# EEZ_DIB_DCP405_r2B6.net
KiCad netlist of a schematic drawn in EAGLE
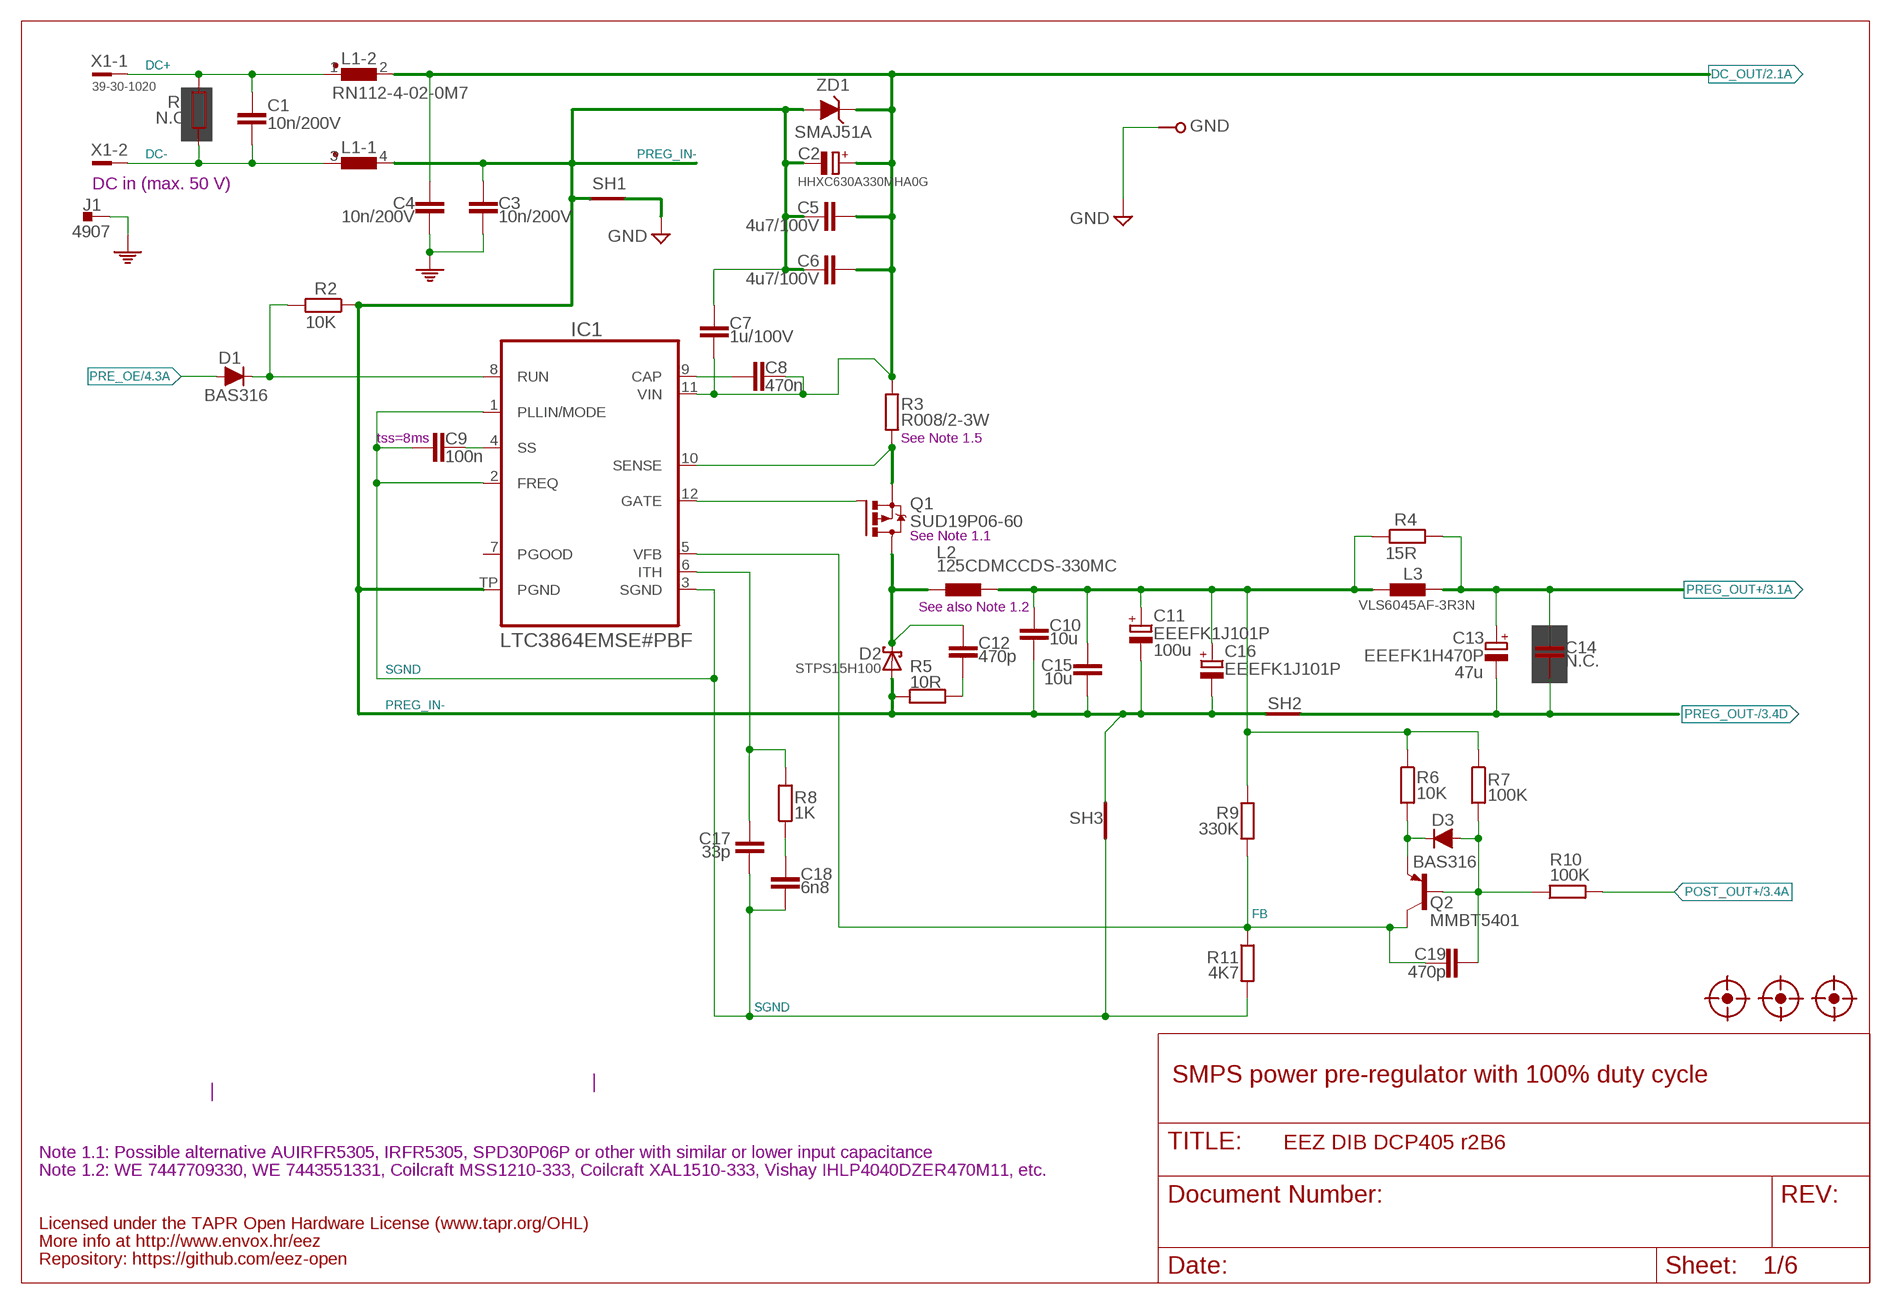
[diagram p0: schematic, sheet 1]
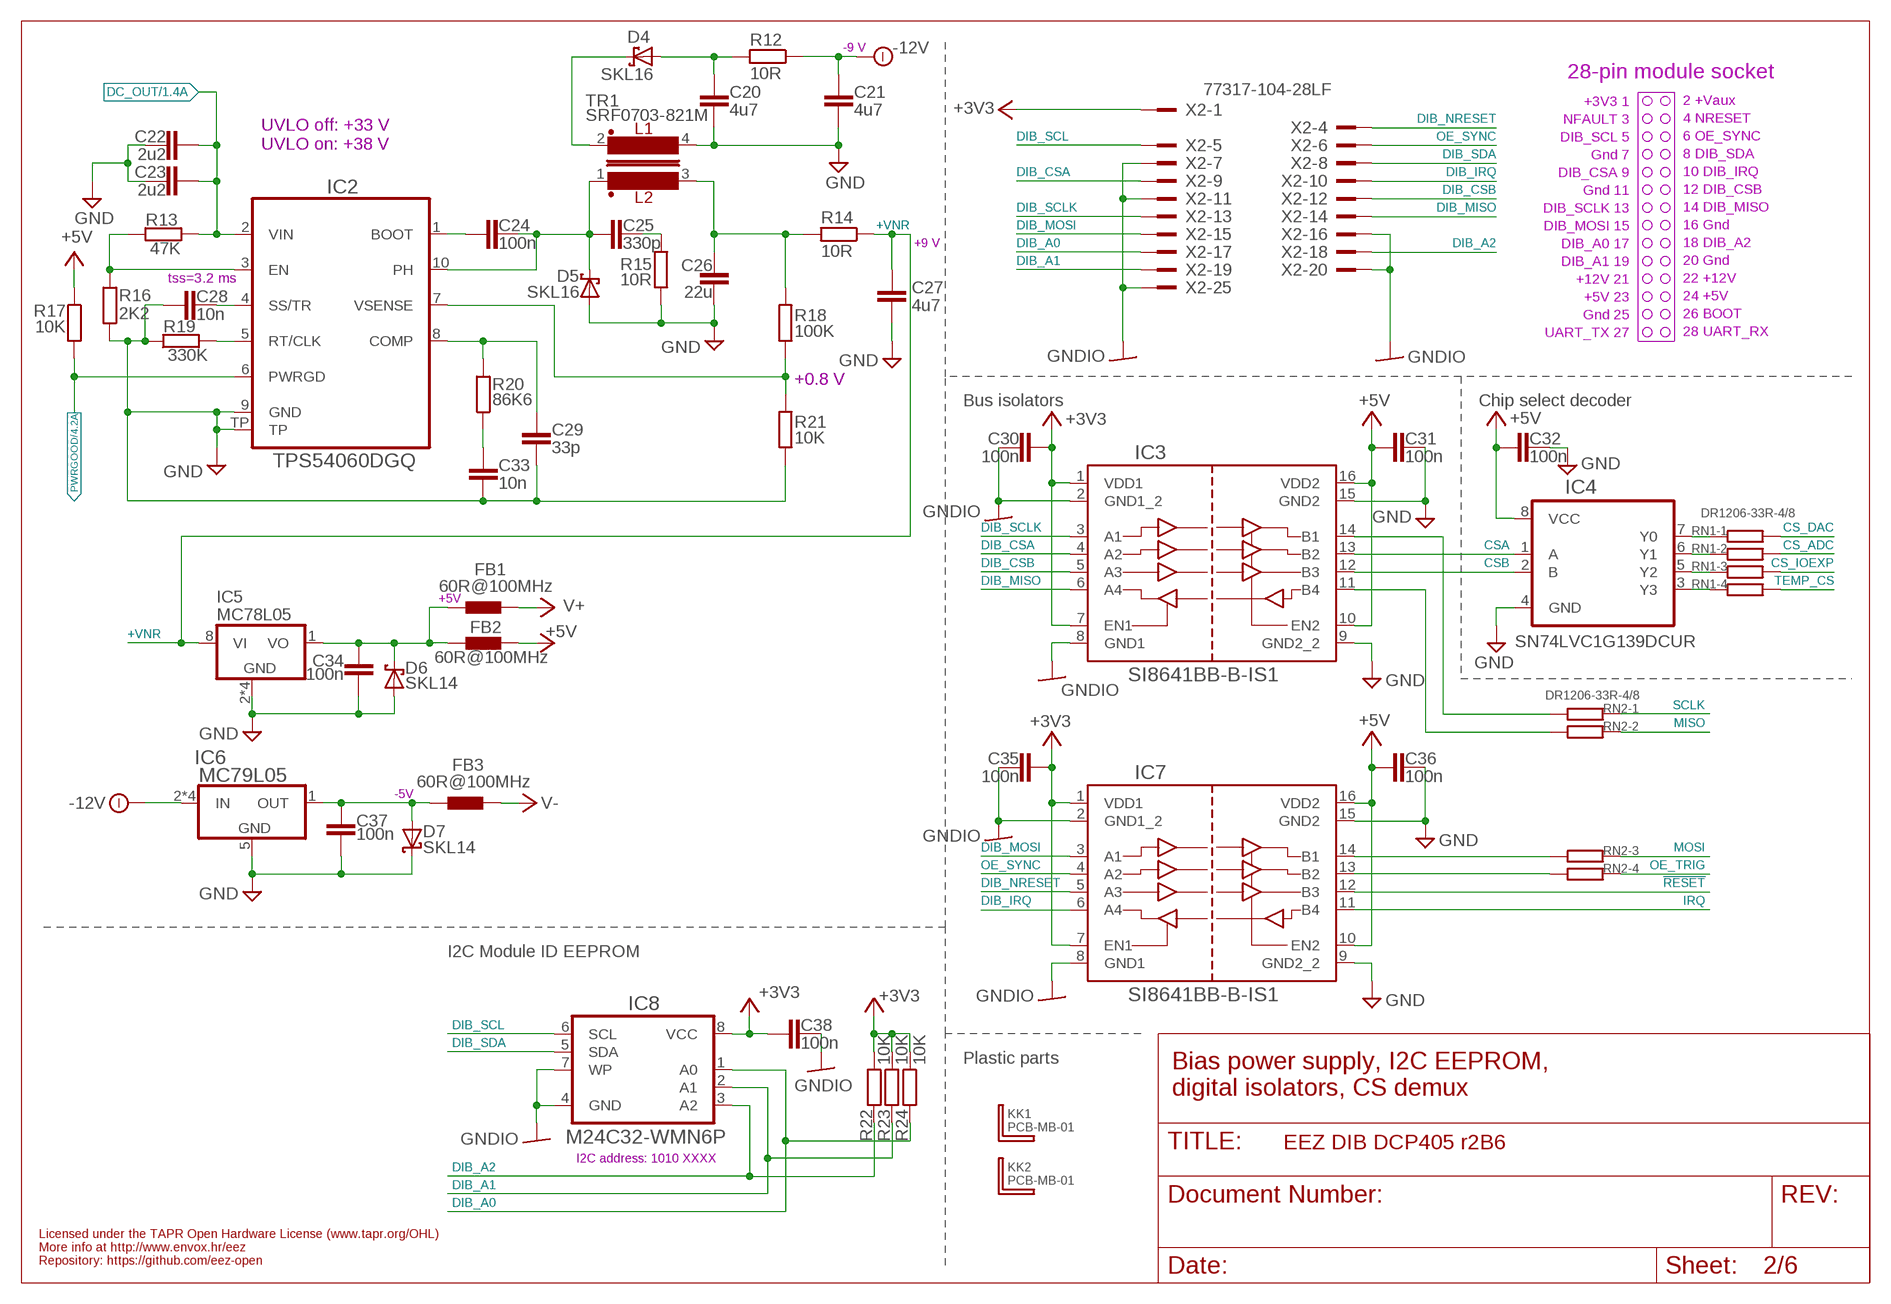
[diagram p1: schematic, sheet 2]
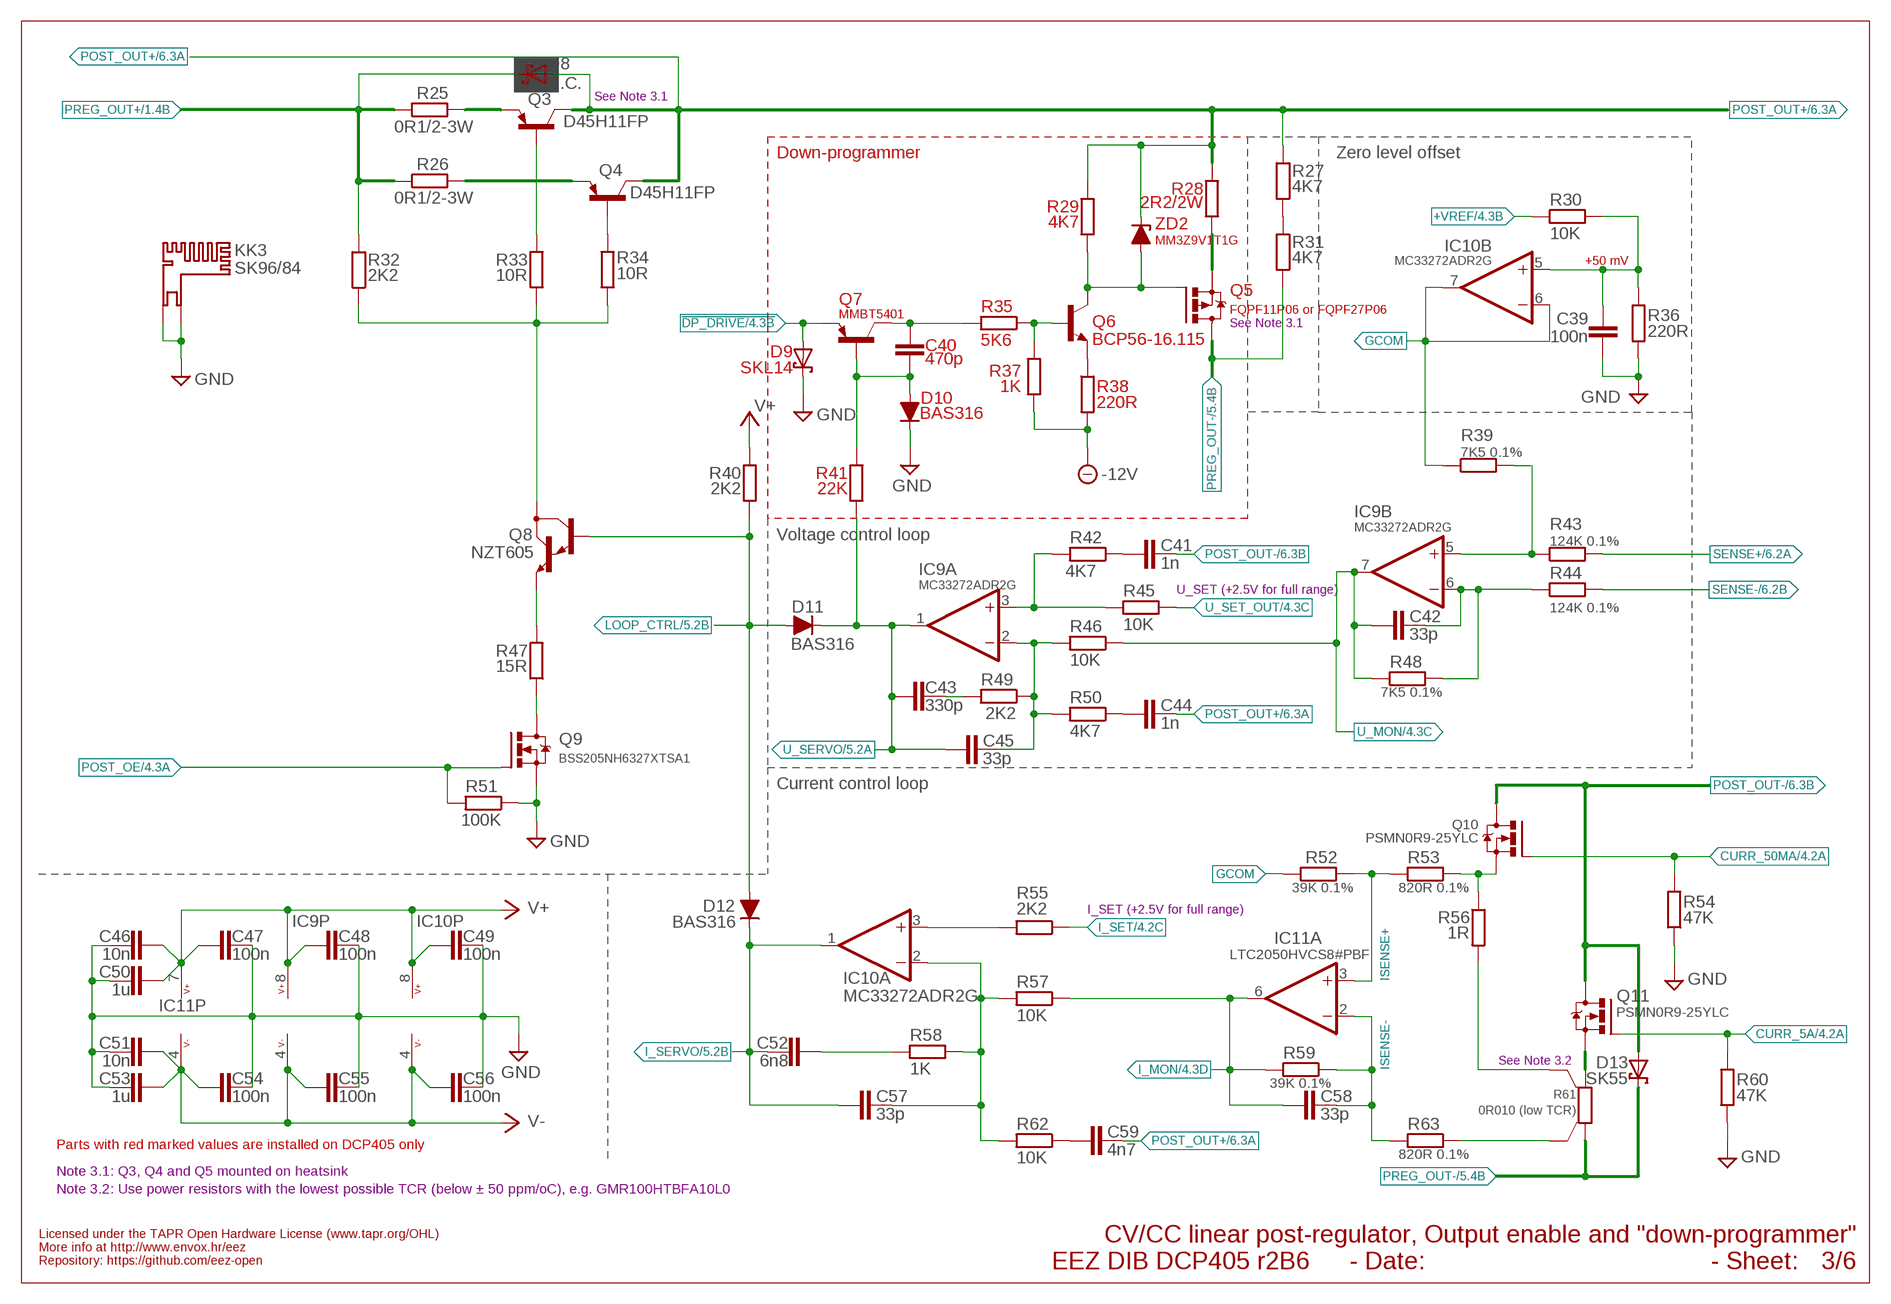
[diagram p2: schematic, sheet 3]
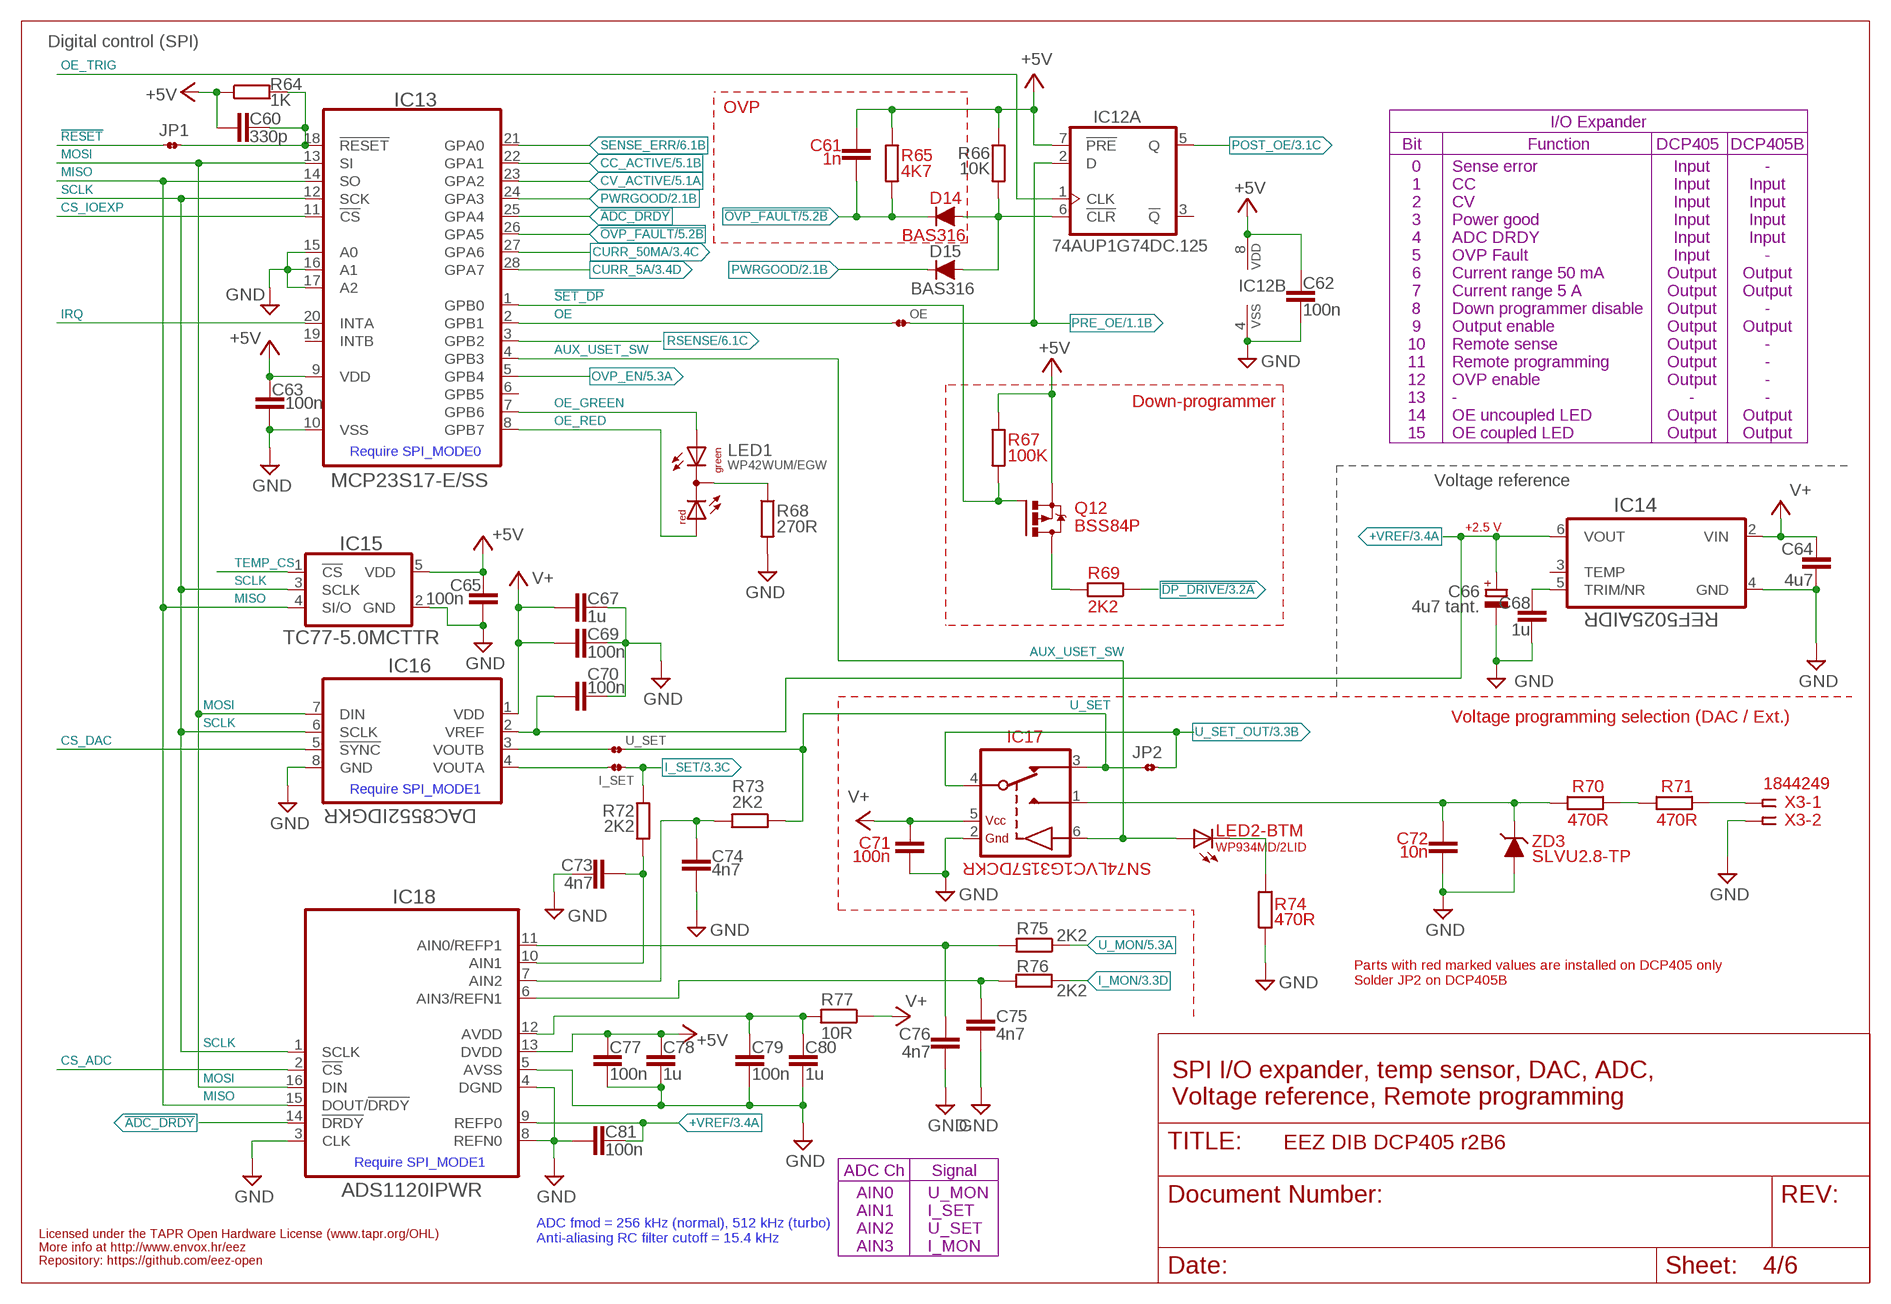
[diagram p3: schematic, sheet 4]
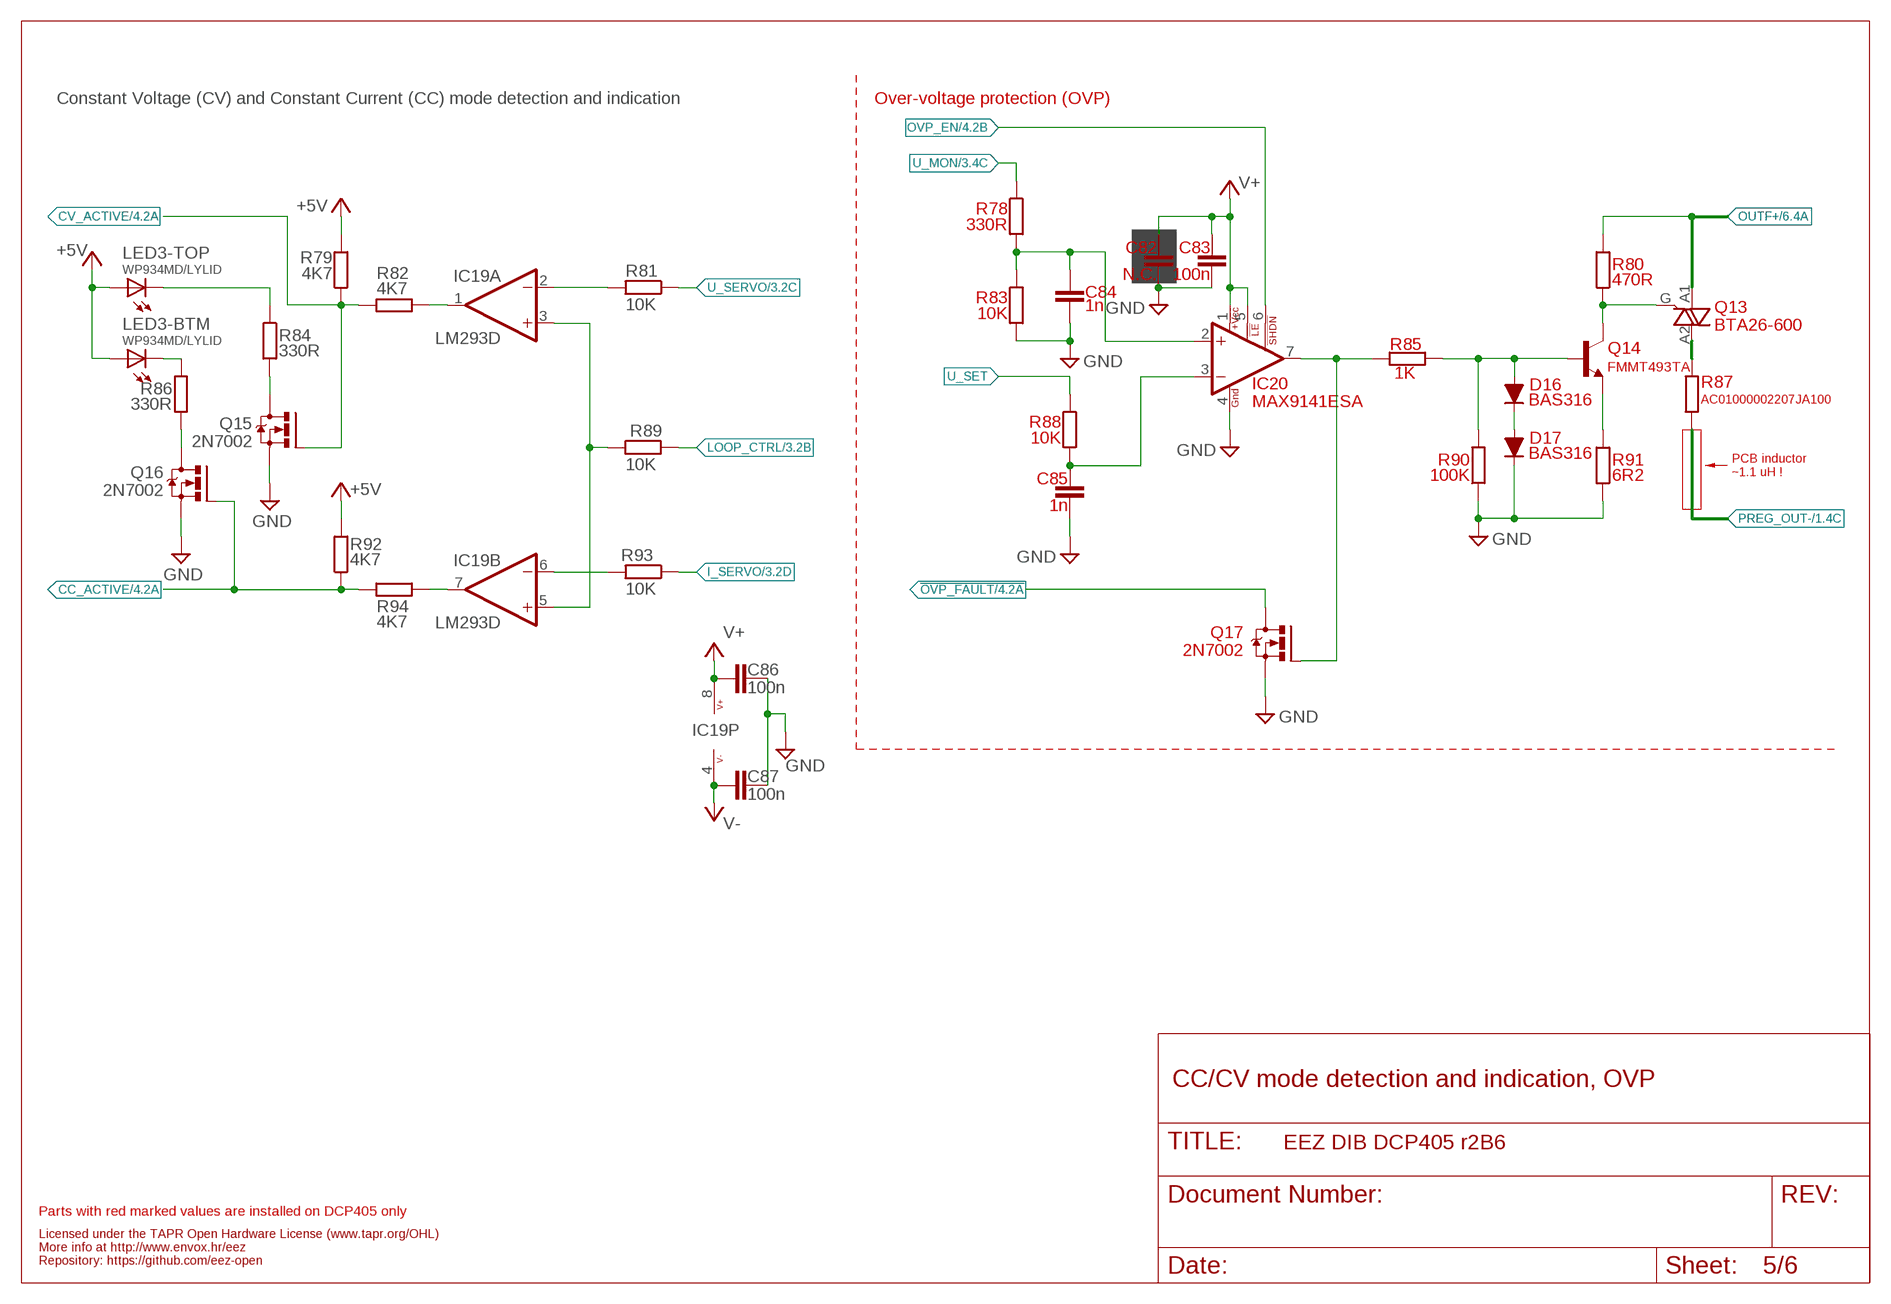
[diagram p4: schematic, sheet 5]
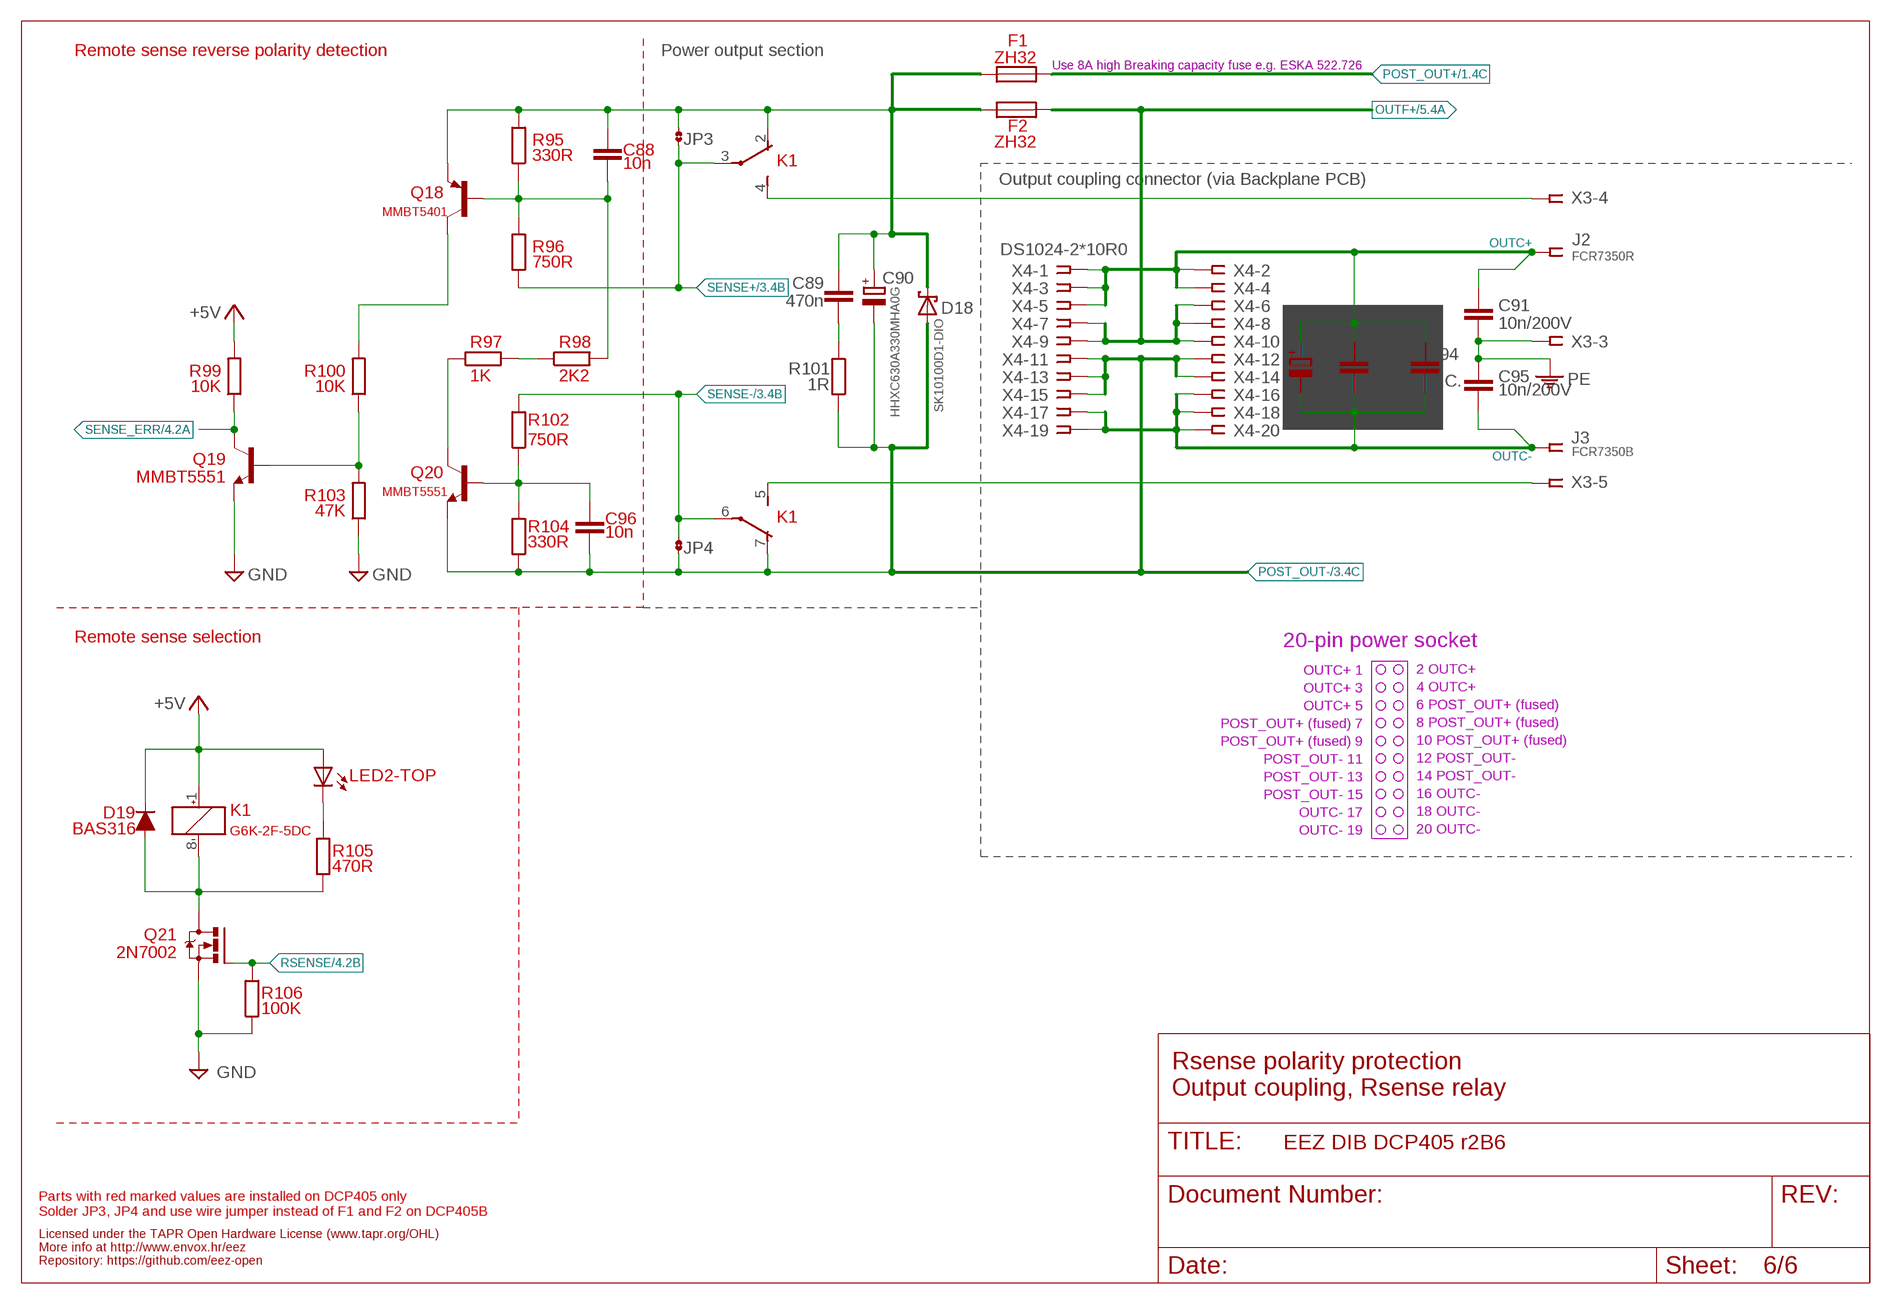
[diagram p5: schematic, sheet 6]

(export (version "E")
  (design (tool "Eeschema 10.0.6"))
  (components
    (comp (ref "C20")
      (value "4u7")
      (footprint "eagle-import:C1206")
      (libsource (lib "eagle-import") (part "C-EUC1206"))
    )
    (comp (ref "C21")
      (value "4u7")
      (footprint "eagle-import:C1206")
      (libsource (lib "eagle-import") (part "C-EUC1206"))
    )
    (comp (ref "C22")
      (value "2u2")
      (footprint "eagle-import:C1206")
      (libsource (lib "eagle-import") (part "C-EUC1206"))
    )
    (comp (ref "C23")
      (value "2u2")
      (footprint "eagle-import:C1206")
      (libsource (lib "eagle-import") (part "C-EUC1206"))
    )
    (comp (ref "C24")
      (value "100n")
      (footprint "eagle-import:C0603")
      (libsource (lib "eagle-import") (part "C-EUC0603"))
    )
    (comp (ref "C25")
      (value "330p")
      (footprint "eagle-import:C0805")
      (libsource (lib "eagle-import") (part "C-EUC0805"))
    )
    (comp (ref "C26")
      (value "22u")
      (footprint "eagle-import:C1210")
      (libsource (lib "eagle-import") (part "C-EUC1210"))
    )
    (comp (ref "C27")
      (value "4u7")
      (footprint "eagle-import:C1206")
      (libsource (lib "eagle-import") (part "C-EUC1206"))
    )
    (comp (ref "C28")
      (value "10n")
      (footprint "eagle-import:C0805")
      (libsource (lib "eagle-import") (part "C-EUC0805"))
    )
    (comp (ref "C29")
      (value "33p")
      (footprint "eagle-import:C0603")
      (libsource (lib "eagle-import") (part "C-EUC0603"))
    )
    (comp (ref "C30")
      (value "100n")
      (footprint "eagle-import:C0603")
      (libsource (lib "eagle-import") (part "C-EUC0603"))
    )
    (comp (ref "C31")
      (value "100n")
      (footprint "eagle-import:C0603")
      (libsource (lib "eagle-import") (part "C-EUC0603"))
    )
    (comp (ref "C32")
      (value "100n")
      (footprint "eagle-import:C0603")
      (libsource (lib "eagle-import") (part "C-EUC0603"))
    )
    (comp (ref "C33")
      (value "10n")
      (footprint "eagle-import:C0805")
      (libsource (lib "eagle-import") (part "C-EUC0805"))
    )
    (comp (ref "C34")
      (value "100n")
      (footprint "eagle-import:C0603")
      (libsource (lib "eagle-import") (part "C-EUC0603"))
    )
    (comp (ref "C35")
      (value "100n")
      (footprint "eagle-import:C0603")
      (libsource (lib "eagle-import") (part "C-EUC0603"))
    )
    (comp (ref "C36")
      (value "100n")
      (footprint "eagle-import:C0603")
      (libsource (lib "eagle-import") (part "C-EUC0603"))
    )
    (comp (ref "C37")
      (value "100n")
      (footprint "eagle-import:C0603")
      (libsource (lib "eagle-import") (part "C-EUC0603"))
    )
    (comp (ref "C38")
      (value "100n")
      (footprint "eagle-import:C0603")
      (libsource (lib "eagle-import") (part "C-EUC0603"))
    )
    (comp (ref "D4")
      (value "SKL16")
      (footprint "eagle-import:SOD123")
      (libsource (lib "eagle-import") (part "SCHOTTKYSOD123"))
    )
    (comp (ref "D5")
      (value "SKL16")
      (footprint "eagle-import:SOD123")
      (libsource (lib "eagle-import") (part "SCHOTTKYSOD123"))
    )
    (comp (ref "D6")
      (value "SKL14")
      (footprint "eagle-import:SOD123")
      (libsource (lib "eagle-import") (part "SCHOTTKYSOD123"))
    )
    (comp (ref "D7")
      (value "SKL14")
      (footprint "eagle-import:SOD123")
      (libsource (lib "eagle-import") (part "SCHOTTKYSOD123"))
    )
    (comp (ref "FB1")
      (value "60R@100MHz")
      (footprint "eagle-import:BEAD0603")
      (libsource (lib "eagle-import") (part "FERRITE_BEAD0603"))
    )
    (comp (ref "FB2")
      (value "60R@100MHz")
      (footprint "eagle-import:BEAD0603")
      (libsource (lib "eagle-import") (part "FERRITE_BEAD0603"))
    )
    (comp (ref "FB3")
      (value "60R@100MHz")
      (footprint "eagle-import:BEAD0603")
      (libsource (lib "eagle-import") (part "FERRITE_BEAD0603"))
    )
    (comp (ref "IC2")
      (value "TPS54060DGQ")
      (footprint "eagle-import:SOP50P490X110-11N")
      (fields (field (name "MPN") "TPS54060ADGQ"))
      (libsource (lib "eagle-import") (part "TPS54060DGQ"))
    )
    (comp (ref "IC3")
      (value "SI8641BB-B-IS1")
      (footprint "eagle-import:SOIC-16")
      (libsource (lib "eagle-import") (part "SI8641NSOIC-16"))
    )
    (comp (ref "IC4")
      (value "SN74LVC1G139DCUR")
      (footprint "eagle-import:DCU8")
      (libsource (lib "eagle-import") (part "SN74LVC1G139-VSSOP"))
    )
    (comp (ref "IC5")
      (value "MC78L05")
      (footprint "eagle-import:SOIC127P600X173-8N")
      (libsource (lib "eagle-import") (part "MC78LXXSOIC8"))
    )
    (comp (ref "IC6")
      (value "MC79L05")
      (footprint "eagle-import:SOIC127P600X173-8N")
      (libsource (lib "eagle-import") (part "MC79LXXSOIC"))
    )
    (comp (ref "IC7")
      (value "SI8641BB-B-IS1")
      (footprint "eagle-import:SOIC-16")
      (libsource (lib "eagle-import") (part "SI8641NSOIC-16"))
    )
    (comp (ref "IC8")
      (value "M24C32-WMN6P")
      (footprint "eagle-import:SOIC127P600X173-8N")
      (libsource (lib "eagle-import") (part "AT24CXXSOIC8"))
    )
    (comp (ref "KK1")
      (value "PCB-MB-01")
      (footprint "eagle-import:PCB-MB")
      (libsource (lib "eagle-import") (part "PCB-MB"))
    )
    (comp (ref "KK2")
      (value "PCB-MB-01")
      (footprint "eagle-import:PCB-MB")
      (libsource (lib "eagle-import") (part "PCB-MB"))
    )
    (comp (ref "R12")
      (value "10R")
      (footprint "eagle-import:R1206")
      (libsource (lib "eagle-import") (part "R-EU_R1206"))
    )
    (comp (ref "R13")
      (value "47K")
      (footprint "eagle-import:R0805")
      (libsource (lib "eagle-import") (part "R-EU_R0805"))
    )
    (comp (ref "R14")
      (value "10R")
      (footprint "eagle-import:R1206")
      (libsource (lib "eagle-import") (part "R-EU_R1206"))
    )
    (comp (ref "R15")
      (value "10R")
      (footprint "eagle-import:R1206")
      (libsource (lib "eagle-import") (part "R-EU_R1206"))
    )
    (comp (ref "R16")
      (value "2K2")
      (footprint "eagle-import:R0805")
      (libsource (lib "eagle-import") (part "R-EU_R0805"))
    )
    (comp (ref "R17")
      (value "10K")
      (footprint "eagle-import:R0805")
      (libsource (lib "eagle-import") (part "R-EU_R0805"))
    )
    (comp (ref "R18")
      (value "100K")
      (footprint "eagle-import:R0805")
      (libsource (lib "eagle-import") (part "R-EU_R0805"))
    )
    (comp (ref "R19")
      (value "330K")
      (footprint "eagle-import:R0805")
      (libsource (lib "eagle-import") (part "R-EU_R0805"))
    )
    (comp (ref "R20")
      (value "86K6")
      (footprint "eagle-import:R0805")
      (libsource (lib "eagle-import") (part "R-EU_R0805"))
    )
    (comp (ref "R21")
      (value "10K")
      (footprint "eagle-import:R0805")
      (libsource (lib "eagle-import") (part "R-EU_R0805"))
    )
    (comp (ref "R22")
      (value "10K")
      (footprint "eagle-import:R0805")
      (libsource (lib "eagle-import") (part "R-EU_R0805"))
    )
    (comp (ref "R23")
      (value "10K")
      (footprint "eagle-import:R0805")
      (libsource (lib "eagle-import") (part "R-EU_R0805"))
    )
    (comp (ref "R24")
      (value "10K")
      (footprint "eagle-import:R0805")
      (libsource (lib "eagle-import") (part "R-EU_R0805"))
    )
    (comp (ref "RN1")
      (value "DR1206-33R-4/8")
      (footprint "eagle-import:CAY16")
      (libsource (lib "eagle-import") (part "R_ARRAY4"))
    )
    (comp (ref "RN2")
      (value "DR1206-33R-4/8")
      (footprint "eagle-import:CAY16")
      (libsource (lib "eagle-import") (part "R_ARRAY4"))
    )
    (comp (ref "TR1")
      (value "SRF0703-821M")
      (footprint "eagle-import:SRF0703")
      (libsource (lib "eagle-import") (part "BOURNS_SRF0703INV"))
    )
    (comp (ref "X2")
      (value "77317-104-28LF")
      (footprint "eagle-import:77317-104-28LF")
      (libsource (lib "eagle-import") (part "77317-104-28LF"))
    )
    (comp (ref "C82")
      (value "N.C.")
      (footprint "eagle-import:C0805")
      (libsource (lib "eagle-import") (part "C-EUC0805"))
    )
    (comp (ref "C83")
      (value "100n")
      (footprint "eagle-import:C0603")
      (libsource (lib "eagle-import") (part "C-EUC0603"))
    )
    (comp (ref "C84")
      (value "1n")
      (footprint "eagle-import:C0805")
      (libsource (lib "eagle-import") (part "C-EUC0805"))
    )
    (comp (ref "C85")
      (value "1n")
      (footprint "eagle-import:C0805")
      (libsource (lib "eagle-import") (part "C-EUC0805"))
    )
    (comp (ref "C86")
      (value "100n")
      (footprint "eagle-import:C0603")
      (libsource (lib "eagle-import") (part "C-EUC0603"))
    )
    (comp (ref "C87")
      (value "100n")
      (footprint "eagle-import:C0603")
      (libsource (lib "eagle-import") (part "C-EUC0603"))
    )
    (comp (ref "D16")
      (value "BAS316")
      (footprint "eagle-import:SOD323-R")
      (libsource (lib "eagle-import") (part "DIODESOD323R"))
    )
    (comp (ref "D17")
      (value "BAS316")
      (footprint "eagle-import:SOD323-R")
      (libsource (lib "eagle-import") (part "DIODESOD323R"))
    )
    (comp (ref "IC19")
      (value "LM293D")
      (footprint "eagle-import:SOIC127P600X173-8N")
      (libsource (lib "eagle-import") (part "LM293D"))
    )
    (comp (ref "IC20")
      (value "MAX9141ESA")
      (footprint "eagle-import:SOIC127P600X173-8N")
      (libsource (lib "eagle-import") (part "MAX9141ESA"))
    )
    (comp (ref "LED3")
      (value "WP934MD/LYLID")
      (footprint "eagle-import:WP934MD")
      (libsource (lib "eagle-import") (part "WP934MD/LYLID"))
    )
    (comp (ref "Q13")
      (value "BTA26-600")
      (footprint "eagle-import:TOP3_TRIAC_NOHOLE")
      (libsource (lib "eagle-import") (part "BTA41-2"))
    )
    (comp (ref "Q14")
      (value "FMMT493TA")
      (footprint "eagle-import:SOT23-BEC")
      (libsource (lib "eagle-import") (part "-NPN-SOT23-BECMMBT5551LT1"))
    )
    (comp (ref "Q15")
      (value "2N7002")
      (footprint "eagle-import:SOT103P240X110-3N")
      (fields (field (name "MPN") "2N7002-7-F"))
      (libsource (lib "eagle-import") (part "2N7002"))
    )
    (comp (ref "Q16")
      (value "2N7002")
      (footprint "eagle-import:SOT103P240X110-3N")
      (fields (field (name "MPN") "2N7002-7-F"))
      (libsource (lib "eagle-import") (part "2N7002"))
    )
    (comp (ref "Q17")
      (value "2N7002")
      (footprint "eagle-import:SOT103P240X110-3N")
      (fields
        (field (name "MPN") "2N7002-7-F")
        (field (name "MPN_1") "2N7002-7-F")
        (field (name "OC_FARNELL") "1713823")
        (field (name "OC_NEWARK") "25R5679")
        (field (name "PACKAGE") "SOT-23-3")
        (field (name "SUPPLIER") "DIODES INC.")
      )
      (libsource (lib "eagle-import") (part "2N7002"))
    )
    (comp (ref "R78")
      (value "330R")
      (footprint "eagle-import:R0805")
      (libsource (lib "eagle-import") (part "R-EU_R0805"))
    )
    (comp (ref "R79")
      (value "4K7")
      (footprint "eagle-import:R0805")
      (libsource (lib "eagle-import") (part "R-EU_R0805"))
    )
    (comp (ref "R80")
      (value "470R")
      (footprint "eagle-import:R0805")
      (libsource (lib "eagle-import") (part "R-EU_R0805"))
    )
    (comp (ref "R81")
      (value "10K")
      (footprint "eagle-import:R0805")
      (libsource (lib "eagle-import") (part "R-EU_R0805"))
    )
    (comp (ref "R82")
      (value "4K7")
      (footprint "eagle-import:R0805")
      (libsource (lib "eagle-import") (part "R-EU_R0805"))
    )
    (comp (ref "R83")
      (value "10K")
      (footprint "eagle-import:R0805")
      (libsource (lib "eagle-import") (part "R-EU_R0805"))
    )
    (comp (ref "R84")
      (value "330R")
      (footprint "eagle-import:R0805")
      (libsource (lib "eagle-import") (part "R-EU_R0805"))
    )
    (comp (ref "R85")
      (value "1K")
      (footprint "eagle-import:R0805")
      (libsource (lib "eagle-import") (part "R-EU_R0805"))
    )
    (comp (ref "R86")
      (value "330R")
      (footprint "eagle-import:R0805")
      (libsource (lib "eagle-import") (part "R-EU_R0805"))
    )
    (comp (ref "R87")
      (value "AC01000002207JA100")
      (footprint "eagle-import:0411_15")
      (libsource (lib "eagle-import") (part "R-EU_0411/15"))
    )
    (comp (ref "R88")
      (value "10K")
      (footprint "eagle-import:R0805")
      (libsource (lib "eagle-import") (part "R-EU_R0805"))
    )
    (comp (ref "R89")
      (value "10K")
      (footprint "eagle-import:R0805")
      (libsource (lib "eagle-import") (part "R-EU_R0805"))
    )
    (comp (ref "R90")
      (value "100K")
      (footprint "eagle-import:R0805")
      (libsource (lib "eagle-import") (part "R-EU_R0805"))
    )
    (comp (ref "R91")
      (value "6R2")
      (footprint "eagle-import:R0805")
      (libsource (lib "eagle-import") (part "R-EU_R0805"))
    )
    (comp (ref "R92")
      (value "4K7")
      (footprint "eagle-import:R0805")
      (libsource (lib "eagle-import") (part "R-EU_R0805"))
    )
    (comp (ref "R93")
      (value "10K")
      (footprint "eagle-import:R0805")
      (libsource (lib "eagle-import") (part "R-EU_R0805"))
    )
    (comp (ref "R94")
      (value "4K7")
      (footprint "eagle-import:R0805")
      (libsource (lib "eagle-import") (part "R-EU_R0805"))
    )
    (comp (ref "C39")
      (value "100n")
      (footprint "eagle-import:C0603")
      (libsource (lib "eagle-import") (part "C-EUC0603"))
    )
    (comp (ref "C40")
      (value "470p")
      (footprint "eagle-import:C0805")
      (libsource (lib "eagle-import") (part "C-EUC0805"))
    )
    (comp (ref "C41")
      (value "1n")
      (footprint "eagle-import:C0805")
      (libsource (lib "eagle-import") (part "C-EUC0805"))
    )
    (comp (ref "C42")
      (value "33p")
      (footprint "eagle-import:C0805")
      (libsource (lib "eagle-import") (part "C-EUC0805"))
    )
    (comp (ref "C43")
      (value "330p")
      (footprint "eagle-import:C0805")
      (libsource (lib "eagle-import") (part "C-EUC0805"))
    )
    (comp (ref "C44")
      (value "1n")
      (footprint "eagle-import:C0805")
      (libsource (lib "eagle-import") (part "C-EUC0805"))
    )
    (comp (ref "C45")
      (value "33p")
      (footprint "eagle-import:C0805")
      (libsource (lib "eagle-import") (part "C-EUC0805"))
    )
    (comp (ref "C46")
      (value "10n")
      (footprint "eagle-import:C0805")
      (libsource (lib "eagle-import") (part "C-EUC0805"))
    )
    (comp (ref "C47")
      (value "100n")
      (footprint "eagle-import:C0603")
      (libsource (lib "eagle-import") (part "C-EUC0603"))
    )
    (comp (ref "C48")
      (value "100n")
      (footprint "eagle-import:C0603")
      (libsource (lib "eagle-import") (part "C-EUC0603"))
    )
    (comp (ref "C49")
      (value "100n")
      (footprint "eagle-import:C0603")
      (libsource (lib "eagle-import") (part "C-EUC0603"))
    )
    (comp (ref "C50")
      (value "1u")
      (footprint "eagle-import:C0805")
      (libsource (lib "eagle-import") (part "C-EUC0805"))
    )
    (comp (ref "C51")
      (value "10n")
      (footprint "eagle-import:C0805")
      (libsource (lib "eagle-import") (part "C-EUC0805"))
    )
    (comp (ref "C52")
      (value "6n8")
      (footprint "eagle-import:C0805")
      (libsource (lib "eagle-import") (part "C-EUC0805"))
    )
    (comp (ref "C53")
      (value "1u")
      (footprint "eagle-import:C0805")
      (libsource (lib "eagle-import") (part "C-EUC0805"))
    )
    (comp (ref "C54")
      (value "100n")
      (footprint "eagle-import:C0603")
      (libsource (lib "eagle-import") (part "C-EUC0603"))
    )
    (comp (ref "C55")
      (value "100n")
      (footprint "eagle-import:C0603")
      (libsource (lib "eagle-import") (part "C-EUC0603"))
    )
    (comp (ref "C56")
      (value "100n")
      (footprint "eagle-import:C0603")
      (libsource (lib "eagle-import") (part "C-EUC0603"))
    )
    (comp (ref "C57")
      (value "33p")
      (footprint "eagle-import:C0805")
      (libsource (lib "eagle-import") (part "C-EUC0805"))
    )
    (comp (ref "C58")
      (value "33p")
      (footprint "eagle-import:C0805")
      (libsource (lib "eagle-import") (part "C-EUC0805"))
    )
    (comp (ref "C59")
      (value "4n7")
      (footprint "eagle-import:C0805")
      (libsource (lib "eagle-import") (part "C-EUC0805"))
    )
    (comp (ref "D8")
      (value "N.C.")
      (footprint "eagle-import:SOD123")
      (libsource (lib "eagle-import") (part "SCHOTTKYSOD123"))
    )
    (comp (ref "D9")
      (value "SKL14")
      (footprint "eagle-import:SOD123")
      (libsource (lib "eagle-import") (part "SCHOTTKYSOD123"))
    )
    (comp (ref "D10")
      (value "BAS316")
      (footprint "eagle-import:SOD323-R")
      (libsource (lib "eagle-import") (part "DIODESOD323R"))
    )
    (comp (ref "D11")
      (value "BAS316")
      (footprint "eagle-import:SOD323-R")
      (libsource (lib "eagle-import") (part "DIODESOD323R"))
    )
    (comp (ref "D12")
      (value "BAS316")
      (footprint "eagle-import:SOD323-R")
      (libsource (lib "eagle-import") (part "DIODESOD323R"))
    )
    (comp (ref "D13")
      (value "SK55")
      (footprint "eagle-import:SMB")
      (libsource (lib "eagle-import") (part "SCHOTTKYSMB"))
    )
    (comp (ref "IC9")
      (value "MC33272ADR2G")
      (footprint "eagle-import:SOIC127P600X173-8N")
      (libsource (lib "eagle-import") (part "TL072SOIC8"))
    )
    (comp (ref "IC10")
      (value "MC33272ADR2G")
      (footprint "eagle-import:SOIC127P600X173-8N")
      (libsource (lib "eagle-import") (part "TL072SOIC8"))
    )
    (comp (ref "IC11")
      (value "LTC2050HVCS8#PBF")
      (footprint "eagle-import:SOIC127P600X173-8N")
      (libsource (lib "eagle-import") (part "OP27GSZSO8"))
    )
    (comp (ref "KK3")
      (value "SK96/84")
      (footprint "eagle-import:SK96_84")
      (libsource (lib "eagle-import") (part "SK96/84"))
    )
    (comp (ref "Q3")
      (value "D45H11FP")
      (footprint "eagle-import:TO220FP-V")
      (libsource (lib "eagle-import") (part "D45H11-FPV"))
    )
    (comp (ref "Q4")
      (value "D45H11FP")
      (footprint "eagle-import:TO220FP-V")
      (libsource (lib "eagle-import") (part "D45H11-FPV"))
    )
    (comp (ref "Q5")
      (value "FQPF11P06 or FQPF27P06")
      (footprint "eagle-import:TO220FP-V")
      (libsource (lib "eagle-import") (part "P-MOSFET-FPV"))
    )
    (comp (ref "Q6")
      (value "BCP56-16.115")
      (footprint "eagle-import:SOT230P700X180-4N")
      (libsource (lib "eagle-import") (part "BCP56"))
    )
    (comp (ref "Q7")
      (value "MMBT5401")
      (footprint "eagle-import:SOT23-BEC")
      (libsource (lib "eagle-import") (part "-PNP-SOT23-BECBC857B"))
    )
    (comp (ref "Q8")
      (value "NZT605")
      (footprint "eagle-import:SOT230P700X180-4N")
      (libsource (lib "eagle-import") (part "NZT605"))
    )
    (comp (ref "Q9")
      (value "BSS205NH6327XTSA1")
      (footprint "eagle-import:SOT103P240X110-3N")
      (fields
        (field (name "MPN") "2N7002-7-F")
        (field (name "MPN_1") "2N7002-7-F")
        (field (name "OC_FARNELL") "1713823")
        (field (name "OC_NEWARK") "25R5679")
        (field (name "PACKAGE") "SOT-23-3")
        (field (name "SUPPLIER") "DIODES INC.")
      )
      (libsource (lib "eagle-import") (part "2N7002"))
    )
    (comp (ref "Q10")
      (value "PSMN0R9-25YLC")
      (footprint "eagle-import:SOT669")
      (libsource (lib "eagle-import") (part "N-MOSFETLFPAK"))
    )
    (comp (ref "Q11")
      (value "PSMN0R9-25YLC")
      (footprint "eagle-import:SOT669")
      (libsource (lib "eagle-import") (part "N-MOSFETLFPAK"))
    )
    (comp (ref "R25")
      (value "0R1/2-3W")
      (footprint "eagle-import:R2512")
      (libsource (lib "eagle-import") (part "R-EU_R2512"))
    )
    (comp (ref "R26")
      (value "0R1/2-3W")
      (footprint "eagle-import:R2512")
      (libsource (lib "eagle-import") (part "R-EU_R2512"))
    )
    (comp (ref "R27")
      (value "4K7")
      (footprint "eagle-import:R0805")
      (libsource (lib "eagle-import") (part "R-EU_R0805"))
    )
    (comp (ref "R28")
      (value "2R2/2W")
      (footprint "eagle-import:R2512")
      (libsource (lib "eagle-import") (part "R-EU_R2512"))
    )
    (comp (ref "R29")
      (value "4K7")
      (footprint "eagle-import:R0805")
      (libsource (lib "eagle-import") (part "R-EU_R0805"))
    )
    (comp (ref "R30")
      (value "10K")
      (footprint "eagle-import:R0805")
      (libsource (lib "eagle-import") (part "R-EU_R0805"))
    )
    (comp (ref "R31")
      (value "4K7")
      (footprint "eagle-import:R0805")
      (libsource (lib "eagle-import") (part "R-EU_R0805"))
    )
    (comp (ref "R32")
      (value "2K2")
      (footprint "eagle-import:R0805")
      (libsource (lib "eagle-import") (part "R-EU_R0805"))
    )
    (comp (ref "R33")
      (value "10R")
      (footprint "eagle-import:R1206")
      (libsource (lib "eagle-import") (part "R-EU_R1206"))
    )
    (comp (ref "R34")
      (value "10R")
      (footprint "eagle-import:R1206")
      (libsource (lib "eagle-import") (part "R-EU_R1206"))
    )
    (comp (ref "R35")
      (value "5K6")
      (footprint "eagle-import:R0805")
      (libsource (lib "eagle-import") (part "R-EU_R0805"))
    )
    (comp (ref "R36")
      (value "220R")
      (footprint "eagle-import:R0805")
      (libsource (lib "eagle-import") (part "R-EU_R0805"))
    )
    (comp (ref "R37")
      (value "1K")
      (footprint "eagle-import:R0805")
      (libsource (lib "eagle-import") (part "R-EU_R0805"))
    )
    (comp (ref "R38")
      (value "220R")
      (footprint "eagle-import:R0805")
      (libsource (lib "eagle-import") (part "R-EU_R0805"))
    )
    (comp (ref "R39")
      (value "7K5 0.1%")
      (footprint "eagle-import:R0805")
      (libsource (lib "eagle-import") (part "R-EU_R0805"))
    )
    (comp (ref "R40")
      (value "2K2")
      (footprint "eagle-import:R0805")
      (libsource (lib "eagle-import") (part "R-EU_R0805"))
    )
    (comp (ref "R41")
      (value "22K")
      (footprint "eagle-import:R0805")
      (libsource (lib "eagle-import") (part "R-EU_R0805"))
    )
    (comp (ref "R42")
      (value "4K7")
      (footprint "eagle-import:R0805")
      (libsource (lib "eagle-import") (part "R-EU_R0805"))
    )
    (comp (ref "R43")
      (value "124K 0.1%")
      (footprint "eagle-import:R0805")
      (libsource (lib "eagle-import") (part "R-EU_R0805"))
    )
    (comp (ref "R44")
      (value "124K 0.1%")
      (footprint "eagle-import:R0805")
      (libsource (lib "eagle-import") (part "R-EU_R0805"))
    )
    (comp (ref "R45")
      (value "10K")
      (footprint "eagle-import:R0805")
      (libsource (lib "eagle-import") (part "R-EU_R0805"))
    )
    (comp (ref "R46")
      (value "10K")
      (footprint "eagle-import:R0805")
      (libsource (lib "eagle-import") (part "R-EU_R0805"))
    )
    (comp (ref "R47")
      (value "15R")
      (footprint "eagle-import:R1206")
      (libsource (lib "eagle-import") (part "R-EU_R1206"))
    )
    (comp (ref "R48")
      (value "7K5 0.1%")
      (footprint "eagle-import:R0805")
      (libsource (lib "eagle-import") (part "R-EU_R0805"))
    )
    (comp (ref "R49")
      (value "2K2")
      (footprint "eagle-import:R0805")
      (libsource (lib "eagle-import") (part "R-EU_R0805"))
    )
    (comp (ref "R50")
      (value "4K7")
      (footprint "eagle-import:R0805")
      (libsource (lib "eagle-import") (part "R-EU_R0805"))
    )
    (comp (ref "R51")
      (value "100K")
      (footprint "eagle-import:R0805")
      (libsource (lib "eagle-import") (part "R-EU_R0805"))
    )
    (comp (ref "R52")
      (value "39K 0.1%")
      (footprint "eagle-import:R0805")
      (libsource (lib "eagle-import") (part "R-EU_R0805"))
    )
    (comp (ref "R53")
      (value "820R 0.1%")
      (footprint "eagle-import:R0805")
      (libsource (lib "eagle-import") (part "R-EU_R0805"))
    )
    (comp (ref "R54")
      (value "47K")
      (footprint "eagle-import:R0805")
      (libsource (lib "eagle-import") (part "R-EU_R0805"))
    )
    (comp (ref "R55")
      (value "2K2")
      (footprint "eagle-import:R0805")
      (libsource (lib "eagle-import") (part "R-EU_R0805"))
    )
    (comp (ref "R56")
      (value "1R")
      (footprint "eagle-import:R1206")
      (libsource (lib "eagle-import") (part "R-EU_R1206"))
    )
    (comp (ref "R57")
      (value "10K")
      (footprint "eagle-import:R0805")
      (libsource (lib "eagle-import") (part "R-EU_R0805"))
    )
    (comp (ref "R58")
      (value "1K")
      (footprint "eagle-import:R0805")
      (libsource (lib "eagle-import") (part "R-EU_R0805"))
    )
    (comp (ref "R59")
      (value "39K 0.1%")
      (footprint "eagle-import:R0805")
      (libsource (lib "eagle-import") (part "R-EU_R0805"))
    )
    (comp (ref "R60")
      (value "47K")
      (footprint "eagle-import:R0805")
      (libsource (lib "eagle-import") (part "R-EU_R0805"))
    )
    (comp (ref "R61")
      (value "0R010 (low TCR)")
      (footprint "eagle-import:R_2512-4WIRE")
      (libsource (lib "eagle-import") (part "R-EU_4WIRE2512"))
    )
    (comp (ref "R62")
      (value "10K")
      (footprint "eagle-import:R0805")
      (libsource (lib "eagle-import") (part "R-EU_R0805"))
    )
    (comp (ref "R63")
      (value "820R 0.1%")
      (footprint "eagle-import:R0805")
      (libsource (lib "eagle-import") (part "R-EU_R0805"))
    )
    (comp (ref "ZD2")
      (value "MM3Z9V1T1G")
      (footprint "eagle-import:SOD323-R")
      (libsource (lib "eagle-import") (part "ZENER-DIODESOD323R"))
    )
    (comp (ref "C60")
      (value "330p")
      (footprint "eagle-import:C0805")
      (libsource (lib "eagle-import") (part "C-EUC0805"))
    )
    (comp (ref "C61")
      (value "1n")
      (footprint "eagle-import:C0805")
      (libsource (lib "eagle-import") (part "C-EUC0805"))
    )
    (comp (ref "C62")
      (value "100n")
      (footprint "eagle-import:C0603")
      (libsource (lib "eagle-import") (part "C-EUC0603"))
    )
    (comp (ref "C63")
      (value "100n")
      (footprint "eagle-import:C0603")
      (libsource (lib "eagle-import") (part "C-EUC0603"))
    )
    (comp (ref "C64")
      (value "4u7")
      (footprint "eagle-import:C1206")
      (libsource (lib "eagle-import") (part "C-EUC1206"))
    )
    (comp (ref "C65")
      (value "100n")
      (footprint "eagle-import:C0603")
      (libsource (lib "eagle-import") (part "C-EUC0603"))
    )
    (comp (ref "C66")
      (value "4u7 tant.")
      (footprint "eagle-import:EC1206")
      (libsource (lib "eagle-import") (part "ECAP1206"))
    )
    (comp (ref "C67")
      (value "1u")
      (footprint "eagle-import:C0805")
      (libsource (lib "eagle-import") (part "C-EUC0805"))
    )
    (comp (ref "C68")
      (value "1u")
      (footprint "eagle-import:C0805")
      (libsource (lib "eagle-import") (part "C-EUC0805"))
    )
    (comp (ref "C69")
      (value "100n")
      (footprint "eagle-import:C0603")
      (libsource (lib "eagle-import") (part "C-EUC0603"))
    )
    (comp (ref "C70")
      (value "100n")
      (footprint "eagle-import:C0603")
      (libsource (lib "eagle-import") (part "C-EUC0603"))
    )
    (comp (ref "C71")
      (value "100n")
      (footprint "eagle-import:C0603")
      (libsource (lib "eagle-import") (part "C-EUC0603"))
    )
    (comp (ref "C72")
      (value "10n")
      (footprint "eagle-import:C0805")
      (libsource (lib "eagle-import") (part "C-EUC0805"))
    )
    (comp (ref "C73")
      (value "4n7")
      (footprint "eagle-import:C0805")
      (libsource (lib "eagle-import") (part "C-EUC0805"))
    )
    (comp (ref "C74")
      (value "4n7")
      (footprint "eagle-import:C0805")
      (libsource (lib "eagle-import") (part "C-EUC0805"))
    )
    (comp (ref "C75")
      (value "4n7")
      (footprint "eagle-import:C0805")
      (libsource (lib "eagle-import") (part "C-EUC0805"))
    )
    (comp (ref "C76")
      (value "4n7")
      (footprint "eagle-import:C0805")
      (libsource (lib "eagle-import") (part "C-EUC0805"))
    )
    (comp (ref "C77")
      (value "100n")
      (footprint "eagle-import:C0603")
      (libsource (lib "eagle-import") (part "C-EUC0603"))
    )
    (comp (ref "C78")
      (value "1u")
      (footprint "eagle-import:C0805")
      (libsource (lib "eagle-import") (part "C-EUC0805"))
    )
    (comp (ref "C79")
      (value "100n")
      (footprint "eagle-import:C0603")
      (libsource (lib "eagle-import") (part "C-EUC0603"))
    )
    (comp (ref "C80")
      (value "1u")
      (footprint "eagle-import:C0805")
      (libsource (lib "eagle-import") (part "C-EUC0805"))
    )
    (comp (ref "C81")
      (value "100n")
      (footprint "eagle-import:C0603")
      (libsource (lib "eagle-import") (part "C-EUC0603"))
    )
    (comp (ref "D14")
      (value "BAS316")
      (footprint "eagle-import:SOD323-R")
      (libsource (lib "eagle-import") (part "DIODESOD323R"))
    )
    (comp (ref "D15")
      (value "BAS316")
      (footprint "eagle-import:SOD323-R")
      (libsource (lib "eagle-import") (part "DIODESOD323R"))
    )
    (comp (ref "IC12")
      (value "74AUP1G74DC.125")
      (footprint "eagle-import:DCU8")
      (libsource (lib "eagle-import") (part "SN74LVC1G74DCTR-VSSOP"))
    )
    (comp (ref "IC13")
      (value "MCP23S17-E/SS")
      (footprint "eagle-import:SOP65P780X200-28N")
      (libsource (lib "eagle-import") (part "MCP23S17-E/SSSSOP"))
    )
    (comp (ref "IC14")
      (value "REF5025AIDR")
      (footprint "eagle-import:SOIC127P600X175-8N")
      (libsource (lib "eagle-import") (part "REF50XX"))
    )
    (comp (ref "IC15")
      (value "TC77-5.0MCTTR")
      (footprint "eagle-import:SOT23-5")
      (libsource (lib "eagle-import") (part "TC77"))
    )
    (comp (ref "IC16")
      (value "DAC8552IDGKR")
      (footprint "eagle-import:DGK8-M")
      (libsource (lib "eagle-import") (part "DAC8552_DGK_8M"))
    )
    (comp (ref "IC17")
      (value "SN74LVC1G3157DCKR")
      (footprint "eagle-import:SOT65P210X110-6N")
      (libsource (lib "eagle-import") (part "SN74LVC1G3157-DCK"))
    )
    (comp (ref "IC18")
      (value "ADS1120IPWR")
      (footprint "eagle-import:PW(R-PDSO-G16)")
      (libsource (lib "eagle-import") (part "ADS1120TSSOP-16"))
    )
    (comp (ref "I_SET")
      (value "JP2-NOCUT")
      (footprint "eagle-import:JP2-NOCUT")
      (libsource (lib "eagle-import") (part "JP2-NOCUT"))
    )
    (comp (ref "JP1")
      (value "JP2-NOCUT")
      (footprint "eagle-import:JP2-NOCUT")
      (libsource (lib "eagle-import") (part "JP2-NOCUT"))
    )
    (comp (ref "JP2")
      (value "JP2-CUT")
      (footprint "eagle-import:JP2-CUT")
      (libsource (lib "eagle-import") (part "JP2-CUT"))
    )
    (comp (ref "LED1")
      (value "WP42WUM/EGW")
      (footprint "eagle-import:L-42WUM-1EGWT")
      (libsource (lib "eagle-import") (part "LED_L-42WUM/1EGWT"))
    )
    (comp (ref "LED2")
      (value "WP934MD/2LID")
      (footprint "eagle-import:WP934MD")
      (libsource (lib "eagle-import") (part "WP934MD/2LID"))
    )
    (comp (ref "OE")
      (value "JP2-NOCUT")
      (footprint "eagle-import:JP2-NOCUT")
      (libsource (lib "eagle-import") (part "JP2-NOCUT"))
    )
    (comp (ref "Q12")
      (value "BSS84P")
      (footprint "eagle-import:SOT95P237X112-3N")
      (fields (field (name "MPN") "IRLML2246TRPBF"))
      (libsource (lib "eagle-import") (part "IRLML2246TRPBF"))
    )
    (comp (ref "R64")
      (value "1K")
      (footprint "eagle-import:R0805")
      (libsource (lib "eagle-import") (part "R-EU_R0805"))
    )
    (comp (ref "R65")
      (value "4K7")
      (footprint "eagle-import:R0805")
      (libsource (lib "eagle-import") (part "R-EU_R0805"))
    )
    (comp (ref "R66")
      (value "10K")
      (footprint "eagle-import:R0805")
      (libsource (lib "eagle-import") (part "R-EU_R0805"))
    )
    (comp (ref "R67")
      (value "100K")
      (footprint "eagle-import:R0805")
      (libsource (lib "eagle-import") (part "R-EU_R0805"))
    )
    (comp (ref "R68")
      (value "270R")
      (footprint "eagle-import:R0805")
      (libsource (lib "eagle-import") (part "R-EU_R0805"))
    )
    (comp (ref "R69")
      (value "2K2")
      (footprint "eagle-import:R0805")
      (libsource (lib "eagle-import") (part "R-EU_R0805"))
    )
    (comp (ref "R70")
      (value "470R")
      (footprint "eagle-import:R0805")
      (libsource (lib "eagle-import") (part "R-EU_R0805"))
    )
    (comp (ref "R71")
      (value "470R")
      (footprint "eagle-import:R0805")
      (libsource (lib "eagle-import") (part "R-EU_R0805"))
    )
    (comp (ref "R72")
      (value "2K2")
      (footprint "eagle-import:R0805")
      (libsource (lib "eagle-import") (part "R-EU_R0805"))
    )
    (comp (ref "R73")
      (value "2K2")
      (footprint "eagle-import:R0805")
      (libsource (lib "eagle-import") (part "R-EU_R0805"))
    )
    (comp (ref "R74")
      (value "470R")
      (footprint "eagle-import:R0805")
      (libsource (lib "eagle-import") (part "R-EU_R0805"))
    )
    (comp (ref "R75")
      (value "2K2")
      (footprint "eagle-import:R0805")
      (libsource (lib "eagle-import") (part "R-EU_R0805"))
    )
    (comp (ref "R76")
      (value "2K2")
      (footprint "eagle-import:R0805")
      (libsource (lib "eagle-import") (part "R-EU_R0805"))
    )
    (comp (ref "R77")
      (value "10R")
      (footprint "eagle-import:R1206")
      (libsource (lib "eagle-import") (part "R-EU_R1206"))
    )
    (comp (ref "U_SET")
      (value "JP2-NOCUT")
      (footprint "eagle-import:JP2-NOCUT")
      (libsource (lib "eagle-import") (part "JP2-NOCUT"))
    )
    (comp (ref "X3")
      (value "1844249")
      (footprint "eagle-import:MC1,5_5-G-3,5")
      (libsource (lib "eagle-import") (part "MC1,5/5-G-3,5"))
    )
    (comp (ref "ZD3")
      (value "SLVU2.8-TP")
      (footprint "eagle-import:SOT23")
      (libsource (lib "eagle-import") (part "SLVU2.8"))
    )
    (comp (ref "C1")
      (value "10n/200V")
      (footprint "eagle-import:C1206")
      (libsource (lib "eagle-import") (part "C-EUC1206"))
    )
    (comp (ref "C2")
      (value "HHXC630A330MHA0G")
      (footprint "eagle-import:CAPAE830X1050N")
      (libsource (lib "eagle-import") (part "ECAPSMD8.3MM/HA0"))
    )
    (comp (ref "C3")
      (value "10n/200V")
      (footprint "eagle-import:C1206")
      (libsource (lib "eagle-import") (part "C-EUC1206"))
    )
    (comp (ref "C4")
      (value "10n/200V")
      (footprint "eagle-import:C1206")
      (libsource (lib "eagle-import") (part "C-EUC1206"))
    )
    (comp (ref "C5")
      (value "4u7/100V")
      (footprint "eagle-import:C1210")
      (libsource (lib "eagle-import") (part "C-EUC1210"))
    )
    (comp (ref "C6")
      (value "4u7/100V")
      (footprint "eagle-import:C1210")
      (libsource (lib "eagle-import") (part "C-EUC1210"))
    )
    (comp (ref "C7")
      (value "1u/100V")
      (footprint "eagle-import:C1206")
      (libsource (lib "eagle-import") (part "C-EUC1206"))
    )
    (comp (ref "C8")
      (value "470n")
      (footprint "eagle-import:C0805")
      (libsource (lib "eagle-import") (part "C-EUC0805"))
    )
    (comp (ref "C9")
      (value "100n")
      (footprint "eagle-import:C0603")
      (libsource (lib "eagle-import") (part "C-EUC0603"))
    )
    (comp (ref "C10")
      (value "10u")
      (footprint "eagle-import:C1210")
      (libsource (lib "eagle-import") (part "C-EUC1210"))
    )
    (comp (ref "C11")
      (value "EEEFK1J101P")
      (footprint "eagle-import:CAPAE1030X1050N")
      (libsource (lib "eagle-import") (part "ECAP10X10"))
    )
    (comp (ref "C12")
      (value "470p")
      (footprint "eagle-import:C0805")
      (libsource (lib "eagle-import") (part "C-EUC0805"))
    )
    (comp (ref "C13")
      (value "EEEFK1H470P")
      (footprint "eagle-import:CAPAE830X1050N")
      (libsource (lib "eagle-import") (part "ECAPSMD8.3MM/HA0"))
    )
    (comp (ref "C14")
      (value "N.C.")
      (footprint "eagle-import:C0805")
      (libsource (lib "eagle-import") (part "C-EUC0805"))
    )
    (comp (ref "C15")
      (value "10u")
      (footprint "eagle-import:C1210")
      (libsource (lib "eagle-import") (part "C-EUC1210"))
    )
    (comp (ref "C16")
      (value "EEEFK1J101P")
      (footprint "eagle-import:CAPAE1030X1050N")
      (libsource (lib "eagle-import") (part "ECAP10X10"))
    )
    (comp (ref "C17")
      (value "33p")
      (footprint "eagle-import:C0805")
      (libsource (lib "eagle-import") (part "C-EUC0805"))
    )
    (comp (ref "C18")
      (value "6n8")
      (footprint "eagle-import:C0805")
      (libsource (lib "eagle-import") (part "C-EUC0805"))
    )
    (comp (ref "C19")
      (value "470p")
      (footprint "eagle-import:C0805")
      (libsource (lib "eagle-import") (part "C-EUC0805"))
    )
    (comp (ref "D1")
      (value "BAS316")
      (footprint "eagle-import:SOD323-R")
      (libsource (lib "eagle-import") (part "DIODESOD323R"))
    )
    (comp (ref "D2")
      (value "STPS15H100")
      (footprint "eagle-import:TO252-L")
      (libsource (lib "eagle-import") (part "SCHOTTKY-DUAL_A_L"))
    )
    (comp (ref "D3")
      (value "BAS316")
      (footprint "eagle-import:SOD323-R")
      (libsource (lib "eagle-import") (part "DIODESOD323R"))
    )
    (comp (ref "FM1")
      (value "FIDUCIAL_2")
      (footprint "eagle-import:FIDUCIAL_DUAL")
      (libsource (lib "eagle-import") (part "FIDUCIAL_2"))
    )
    (comp (ref "FM2")
      (value "FIDUCIAL_2")
      (footprint "eagle-import:FIDUCIAL_DUAL")
      (libsource (lib "eagle-import") (part "FIDUCIAL_2"))
    )
    (comp (ref "FM3")
      (value "FIDUCIAL_2")
      (footprint "eagle-import:FIDUCIAL_DUAL")
      (libsource (lib "eagle-import") (part "FIDUCIAL_2"))
    )
    (comp (ref "GND")
      (value "PCB_TEST_TABSHIELD")
      (footprint "eagle-import:PCB_SHIELD_TAB")
      (libsource (lib "eagle-import") (part "PCB_TEST_TABSHIELD"))
    )
    (comp (ref "IC1")
      (value "LTC3864EMSE#PBF")
      (footprint "eagle-import:LTC_05-08-1666")
      (libsource (lib "eagle-import") (part "LTC3864"))
    )
    (comp (ref "J1")
      (value "4907")
      (footprint "eagle-import:PCB_TAB-4907")
      (libsource (lib "eagle-import") (part "PCB_TAB-4907"))
    )
    (comp (ref "L1")
      (value "RN112-4-02-0M7")
      (footprint "eagle-import:RN112")
      (libsource (lib "eagle-import") (part "RN112"))
    )
    (comp (ref "L2")
      (value "125CDMCCDS-330MC")
      (footprint "eagle-import:125CDMCC_DS")
      (libsource (lib "eagle-import") (part "125CDMCC/DS"))
    )
    (comp (ref "L3")
      (value "VLS6045AF-3R3N")
      (footprint "eagle-import:COILCRAFT_HPI0630")
      (libsource (lib "eagle-import") (part "COILCRAFT_HPI0630"))
    )
    (comp (ref "Q1")
      (value "SUD19P06-60")
      (footprint "eagle-import:TO229P990X239-3N")
      (libsource (lib "eagle-import") (part "P-MOSFETDPAK"))
    )
    (comp (ref "Q2")
      (value "MMBT5401")
      (footprint "eagle-import:SOT23-BEC")
      (libsource (lib "eagle-import") (part "-PNP-SOT23-BECBC857B"))
    )
    (comp (ref "R1")
      (value "N.C.")
      (footprint "eagle-import:R2512")
      (libsource (lib "eagle-import") (part "R-EU_R2512"))
    )
    (comp (ref "R2")
      (value "10K")
      (footprint "eagle-import:R0805")
      (libsource (lib "eagle-import") (part "R-EU_R0805"))
    )
    (comp (ref "R3")
      (value "R008/2-3W")
      (footprint "eagle-import:R2512")
      (libsource (lib "eagle-import") (part "R-EU_R2512"))
    )
    (comp (ref "R4")
      (value "15R")
      (footprint "eagle-import:R1206")
      (libsource (lib "eagle-import") (part "R-EU_R1206"))
    )
    (comp (ref "R5")
      (value "10R")
      (footprint "eagle-import:R1206")
      (libsource (lib "eagle-import") (part "R-EU_R1206"))
    )
    (comp (ref "R6")
      (value "10K")
      (footprint "eagle-import:R0805")
      (libsource (lib "eagle-import") (part "R-EU_R0805"))
    )
    (comp (ref "R7")
      (value "100K")
      (footprint "eagle-import:R0805")
      (libsource (lib "eagle-import") (part "R-EU_R0805"))
    )
    (comp (ref "R8")
      (value "1K")
      (footprint "eagle-import:R0805")
      (libsource (lib "eagle-import") (part "R-EU_R0805"))
    )
    (comp (ref "R9")
      (value "330K")
      (footprint "eagle-import:R0805")
      (libsource (lib "eagle-import") (part "R-EU_R0805"))
    )
    (comp (ref "R10")
      (value "100K")
      (footprint "eagle-import:R0805")
      (libsource (lib "eagle-import") (part "R-EU_R0805"))
    )
    (comp (ref "R11")
      (value "4K7")
      (footprint "eagle-import:R0805")
      (libsource (lib "eagle-import") (part "R-EU_R0805"))
    )
    (comp (ref "SH1")
      (value "SHORTNOHOLE")
      (footprint "eagle-import:SHORT_NOHOLE")
      (libsource (lib "eagle-import") (part "SHORTNOHOLE"))
    )
    (comp (ref "SH2")
      (value "Pgnd to Pout- short")
      (footprint "eagle-import:SHORT_NOHOLE")
      (libsource (lib "eagle-import") (part "SHORTNOHOLE"))
    )
    (comp (ref "SH3")
      (value "Sgnd to Pgnd short")
      (footprint "eagle-import:SHORT_NOHOLE")
      (libsource (lib "eagle-import") (part "SHORTNOHOLE"))
    )
    (comp (ref "X1")
      (value "39-30-1020")
      (footprint "eagle-import:MINIFIT_39301020")
      (libsource (lib "eagle-import") (part "MINIFIT_39301020"))
    )
    (comp (ref "ZD1")
      (value "SMAJ51A")
      (footprint "eagle-import:DO214AA")
      (libsource (lib "eagle-import") (part "P6SMB68A"))
    )
    (comp (ref "C88")
      (value "10n")
      (footprint "eagle-import:C0805")
      (libsource (lib "eagle-import") (part "C-EUC0805"))
    )
    (comp (ref "C89")
      (value "470n")
      (footprint "eagle-import:C1206")
      (libsource (lib "eagle-import") (part "C-EUC1206"))
    )
    (comp (ref "C90")
      (value "HHXC630A330MHA0G")
      (footprint "eagle-import:CAPAE830X1050N")
      (libsource (lib "eagle-import") (part "ECAPSMD8.3MM/HA0"))
    )
    (comp (ref "C91")
      (value "10n/200V")
      (footprint "eagle-import:C1206")
      (libsource (lib "eagle-import") (part "C-EUC1206"))
    )
    (comp (ref "C92")
      (value "N.C.")
      (footprint "eagle-import:ECAP2_5")
      (libsource (lib "eagle-import") (part "ECAP2G/5"))
    )
    (comp (ref "C93")
      (value "N.C.")
      (footprint "eagle-import:C0805")
      (libsource (lib "eagle-import") (part "C-EUC0805"))
    )
    (comp (ref "C94")
      (value "N.C.")
      (footprint "eagle-import:C0805")
      (libsource (lib "eagle-import") (part "C-EUC0805"))
    )
    (comp (ref "C95")
      (value "10n/200V")
      (footprint "eagle-import:C1206")
      (libsource (lib "eagle-import") (part "C-EUC1206"))
    )
    (comp (ref "C96")
      (value "10n")
      (footprint "eagle-import:C0805")
      (libsource (lib "eagle-import") (part "C-EUC0805"))
    )
    (comp (ref "D18")
      (value "SK10100D1-DIO")
      (footprint "eagle-import:TO252-L")
      (libsource (lib "eagle-import") (part "SCHOTTKY-DUAL_A_L"))
    )
    (comp (ref "D19")
      (value "BAS316")
      (footprint "eagle-import:SOD323-R")
      (libsource (lib "eagle-import") (part "DIODESOD323R"))
    )
    (comp (ref "F1")
      (value "ZH32")
      (footprint "eagle-import:ZH32")
      (libsource (lib "eagle-import") (part "ZH32"))
    )
    (comp (ref "F2")
      (value "ZH32")
      (footprint "eagle-import:ZH32")
      (libsource (lib "eagle-import") (part "ZH32"))
    )
    (comp (ref "J2")
      (value "FCR7350R")
      (footprint "eagle-import:S16N-PC")
      (libsource (lib "eagle-import") (part "BINDING_POSTCLIFF"))
    )
    (comp (ref "J3")
      (value "FCR7350B")
      (footprint "eagle-import:S16N-PC")
      (libsource (lib "eagle-import") (part "BINDING_POSTCLIFF"))
    )
    (comp (ref "JP3")
      (value "JP2-CUT")
      (footprint "eagle-import:JP2-CUT")
      (libsource (lib "eagle-import") (part "JP2-CUT"))
    )
    (comp (ref "JP4")
      (value "JP2-CUT")
      (footprint "eagle-import:JP2-CUT")
      (libsource (lib "eagle-import") (part "JP2-CUT"))
    )
    (comp (ref "K1")
      (value "G6K-2F-5DC")
      (footprint "eagle-import:G6K-2F")
      (fields
        (field (name "MF") "OMRON COMPONENTS USA")
        (field (name "MPN") "G6K-2F DC24")
        (field (name "MF_1") "OMRON COMPONENTS USA")
        (field (name "MPN_1") "G6K-2F DC24")
        (field (name "OC_FARNELL") "1690427")
        (field (name "OC_NEWARK") "36K7467")
      )
      (libsource (lib "eagle-import") (part "G6K-2F"))
    )
    (comp (ref "Q18")
      (value "MMBT5401")
      (footprint "eagle-import:SOT23-BEC")
      (libsource (lib "eagle-import") (part "-PNP-SOT23-BECBC857B"))
    )
    (comp (ref "Q19")
      (value "MMBT5551")
      (footprint "eagle-import:SOT23-BEC")
      (libsource (lib "eagle-import") (part "-NPN-SOT23-BECMMBT5551LT1"))
    )
    (comp (ref "Q20")
      (value "MMBT5551")
      (footprint "eagle-import:SOT23-BEC")
      (libsource (lib "eagle-import") (part "-NPN-SOT23-BECMMBT5551LT1"))
    )
    (comp (ref "Q21")
      (value "2N7002")
      (footprint "eagle-import:SOT103P240X110-3N")
      (fields
        (field (name "MPN") "2N7002-7-F")
        (field (name "MPN_1") "2N7002-7-F")
        (field (name "OC_FARNELL") "1713823")
        (field (name "OC_NEWARK") "25R5679")
        (field (name "PACKAGE") "SOT-23-3")
        (field (name "SUPPLIER") "DIODES INC.")
      )
      (libsource (lib "eagle-import") (part "2N7002"))
    )
    (comp (ref "R95")
      (value "330R")
      (footprint "eagle-import:R0805")
      (libsource (lib "eagle-import") (part "R-EU_R0805"))
    )
    (comp (ref "R96")
      (value "750R")
      (footprint "eagle-import:R0805")
      (libsource (lib "eagle-import") (part "R-EU_R0805"))
    )
    (comp (ref "R97")
      (value "1K")
      (footprint "eagle-import:R0805")
      (libsource (lib "eagle-import") (part "R-EU_R0805"))
    )
    (comp (ref "R98")
      (value "2K2")
      (footprint "eagle-import:R0805")
      (libsource (lib "eagle-import") (part "R-EU_R0805"))
    )
    (comp (ref "R99")
      (value "10K")
      (footprint "eagle-import:R0805")
      (libsource (lib "eagle-import") (part "R-EU_R0805"))
    )
    (comp (ref "R100")
      (value "10K")
      (footprint "eagle-import:R0805")
      (libsource (lib "eagle-import") (part "R-EU_R0805"))
    )
    (comp (ref "R101")
      (value "1R")
      (footprint "eagle-import:R0805")
      (libsource (lib "eagle-import") (part "R-EU_R0805"))
    )
    (comp (ref "R102")
      (value "750R")
      (footprint "eagle-import:R0805")
      (libsource (lib "eagle-import") (part "R-EU_R0805"))
    )
    (comp (ref "R103")
      (value "47K")
      (footprint "eagle-import:R0805")
      (libsource (lib "eagle-import") (part "R-EU_R0805"))
    )
    (comp (ref "R104")
      (value "330R")
      (footprint "eagle-import:R0805")
      (libsource (lib "eagle-import") (part "R-EU_R0805"))
    )
    (comp (ref "R105")
      (value "470R")
      (footprint "eagle-import:R0805")
      (libsource (lib "eagle-import") (part "R-EU_R0805"))
    )
    (comp (ref "R106")
      (value "100K")
      (footprint "eagle-import:R0805")
      (libsource (lib "eagle-import") (part "R-EU_R0805"))
    )
    (comp (ref "X4")
      (value "DS1024-2*10R0")
      (footprint "eagle-import:SSW-110-02-T-D-RA")
      (libsource (lib "eagle-import") (part "SSW-110-02-T-D-RA"))
    )
  )
  (nets
    (net (code "1") (name "+3V3") (class "Default")
      (node (ref "C30") (pin "1") (pinfunction "1_1") (pintype "passive"))
      (node (ref "C35") (pin "1") (pinfunction "1_1") (pintype "passive"))
      (node (ref "C38") (pin "2") (pinfunction "2_2") (pintype "passive"))
      (node (ref "IC3") (pin "1") (pinfunction "VDD1_1") (pintype "passive"))
      (node (ref "IC3") (pin "7") (pinfunction "EN1_7") (pintype "input"))
      (node (ref "IC7") (pin "1") (pinfunction "VDD1_1") (pintype "passive"))
      (node (ref "IC7") (pin "7") (pinfunction "EN1_7") (pintype "input"))
      (node (ref "IC8") (pin "8") (pinfunction "VCC_8") (pintype "power_in"))
      (node (ref "R22") (pin "1") (pinfunction "1_1") (pintype "passive"))
      (node (ref "R23") (pin "1") (pinfunction "1_1") (pintype "passive"))
      (node (ref "R24") (pin "1") (pinfunction "1_1") (pintype "passive"))
      (node (ref "X2") (pin "1") (pinfunction "1_1") (pintype "passive"))
    )
    (net (code "2") (name "+5V") (class "Default")
      (node (ref "C31") (pin "2") (pinfunction "2_2") (pintype "passive"))
      (node (ref "C32") (pin "1") (pinfunction "1_1") (pintype "passive"))
      (node (ref "C36") (pin "2") (pinfunction "2_2") (pintype "passive"))
      (node (ref "C60") (pin "2") (pinfunction "2_2") (pintype "passive"))
      (node (ref "C61") (pin "2") (pinfunction "2_2") (pintype "passive"))
      (node (ref "C62") (pin "2") (pinfunction "2_2") (pintype "passive"))
      (node (ref "C63") (pin "1") (pinfunction "1_1") (pintype "passive"))
      (node (ref "C65") (pin "1") (pinfunction "1_1") (pintype "passive"))
      (node (ref "C77") (pin "2") (pinfunction "2_2") (pintype "passive"))
      (node (ref "C78") (pin "2") (pinfunction "2_2") (pintype "passive"))
      (node (ref "D19") (pin "C") (pinfunction "C_C") (pintype "passive"))
      (node (ref "FB2") (pin "P$2") (pinfunction "2_P$2") (pintype "passive"))
      (node (ref "IC12") (pin "7") (pinfunction "~{PRE}_7") (pintype "input"))
      (node (ref "IC12") (pin "8") (pinfunction "VDD_8") (pintype "power_in"))
      (node (ref "IC13") (pin "9") (pinfunction "VDD_9") (pintype "power_in"))
      (node (ref "IC15") (pin "5") (pinfunction "VDD_5") (pintype "passive"))
      (node (ref "IC18") (pin "13") (pinfunction "DVDD_13") (pintype "power_in"))
      (node (ref "IC3") (pin "10") (pinfunction "EN2_10") (pintype "input"))
      (node (ref "IC3") (pin "16") (pinfunction "VDD2_16") (pintype "passive"))
      (node (ref "IC4") (pin "8") (pinfunction "VCC_8") (pintype "passive"))
      (node (ref "IC7") (pin "10") (pinfunction "EN2_10") (pintype "input"))
      (node (ref "IC7") (pin "16") (pinfunction "VDD2_16") (pintype "passive"))
      (node (ref "K1") (pin "1") (pinfunction "+_1") (pintype "passive"))
      (node (ref "LED2") (pin "TA") (pinfunction "A_TA") (pintype "passive"))
      (node (ref "LED3") (pin "BA") (pinfunction "A_BA") (pintype "passive"))
      (node (ref "LED3") (pin "TA") (pinfunction "A_TA") (pintype "passive"))
      (node (ref "Q12") (pin "2") (pinfunction "S_2") (pintype "passive"))
      (node (ref "R17") (pin "1") (pinfunction "1_1") (pintype "passive"))
      (node (ref "R64") (pin "1") (pinfunction "1_1") (pintype "passive"))
      (node (ref "R65") (pin "1") (pinfunction "1_1") (pintype "passive"))
      (node (ref "R66") (pin "1") (pinfunction "1_1") (pintype "passive"))
      (node (ref "R67") (pin "1") (pinfunction "1_1") (pintype "passive"))
      (node (ref "R79") (pin "2") (pinfunction "2_2") (pintype "passive"))
      (node (ref "R92") (pin "2") (pinfunction "2_2") (pintype "passive"))
      (node (ref "R99") (pin "2") (pinfunction "2_2") (pintype "passive"))
    )
    (net (code "3") (name "+VNR") (class "Default")
      (node (ref "C27") (pin "1") (pinfunction "1_1") (pintype "passive"))
      (node (ref "IC5") (pin "8") (pinfunction "VI_8") (pintype "input"))
      (node (ref "R14") (pin "1") (pinfunction "1_1") (pintype "passive"))
    )
    (net (code "4") (name "+VREF") (class "Default")
      (node (ref "C66") (pin "+") (pinfunction "+_+") (pintype "passive"))
      (node (ref "C70") (pin "2") (pinfunction "2_2") (pintype "passive"))
      (node (ref "C81") (pin "2") (pinfunction "2_2") (pintype "passive"))
      (node (ref "IC14") (pin "6") (pinfunction "VOUT_6") (pintype "output"))
      (node (ref "IC16") (pin "2") (pinfunction "VREF_2") (pintype "input"))
      (node (ref "IC18") (pin "9") (pinfunction "REFP0_9") (pintype "input"))
      (node (ref "R30") (pin "1") (pinfunction "1_1") (pintype "passive"))
    )
    (net (code "5") (name "-12V") (class "Default")
      (node (ref "C21") (pin "1") (pinfunction "1_1") (pintype "passive"))
      (node (ref "IC6") (pin "2") (pinfunction "IN_2") (pintype "input"))
      (node (ref "IC6") (pin "3") (pinfunction "IN_3") (pintype "input"))
      (node (ref "IC6") (pin "6") (pinfunction "IN_6") (pintype "input"))
      (node (ref "IC6") (pin "7") (pinfunction "IN_7") (pintype "input"))
      (node (ref "R12") (pin "1") (pinfunction "1_1") (pintype "passive"))
      (node (ref "R37") (pin "2") (pinfunction "2_2") (pintype "passive"))
      (node (ref "R38") (pin "2") (pinfunction "2_2") (pintype "passive"))
    )
    (net (code "6") (name "AUX_USET_SW") (class "Default")
      (node (ref "IC13") (pin "4") (pinfunction "GPB3_4") (pintype "bidirectional"))
      (node (ref "IC17") (pin "6") (pinfunction "CTRL_6") (pintype "input"))
      (node (ref "LED2") (pin "BA") (pinfunction "A_BA") (pintype "passive"))
    )
    (net (code "7") (name "CC_ACTIVE") (class "Default")
      (node (ref "IC13") (pin "22") (pinfunction "GPA1_22") (pintype "bidirectional"))
      (node (ref "Q16") (pin "1") (pinfunction "G_1") (pintype "passive"))
      (node (ref "R92") (pin "1") (pinfunction "1_1") (pintype "passive"))
      (node (ref "R94") (pin "2") (pinfunction "2_2") (pintype "passive"))
    )
    (net (code "8") (name "CSA") (class "Default")
      (node (ref "IC3") (pin "13") (pinfunction "B2_13") (pintype "output"))
      (node (ref "IC4") (pin "1") (pinfunction "A_1") (pintype "input"))
    )
    (net (code "9") (name "CSB") (class "Default")
      (node (ref "IC3") (pin "12") (pinfunction "B3_12") (pintype "output"))
      (node (ref "IC4") (pin "2") (pinfunction "B_2") (pintype "input"))
    )
    (net (code "10") (name "CS_ADC") (class "Default")
      (node (ref "IC18") (pin "2") (pinfunction "~{CS}_2") (pintype "input"))
      (node (ref "RN1") (pin "7") (pinfunction "2_7") (pintype "passive"))
    )
    (net (code "11") (name "CS_DAC") (class "Default")
      (node (ref "IC16") (pin "5") (pinfunction "~{SYNC}_5") (pintype "input"))
      (node (ref "RN1") (pin "8") (pinfunction "2_8") (pintype "passive"))
    )
    (net (code "12") (name "CS_IOEXP") (class "Default")
      (node (ref "IC13") (pin "11") (pinfunction "~{CS}_11") (pintype "input"))
      (node (ref "RN1") (pin "6") (pinfunction "2_6") (pintype "passive"))
    )
    (net (code "13") (name "CURR_5A") (class "Default")
      (node (ref "IC13") (pin "28") (pinfunction "GPA7_28") (pintype "bidirectional"))
      (node (ref "Q11") (pin "4") (pinfunction "G_4") (pintype "passive"))
      (node (ref "R60") (pin "2") (pinfunction "2_2") (pintype "passive"))
    )
    (net (code "14") (name "CURR_50MA") (class "Default")
      (node (ref "IC13") (pin "27") (pinfunction "GPA6_27") (pintype "bidirectional"))
      (node (ref "Q10") (pin "4") (pinfunction "G_4") (pintype "passive"))
      (node (ref "R54") (pin "2") (pinfunction "2_2") (pintype "passive"))
    )
    (net (code "15") (name "CV_ACTIVE") (class "Default")
      (node (ref "IC13") (pin "23") (pinfunction "GPA2_23") (pintype "bidirectional"))
      (node (ref "Q15") (pin "1") (pinfunction "G_1") (pintype "passive"))
      (node (ref "R79") (pin "1") (pinfunction "1_1") (pintype "passive"))
      (node (ref "R82") (pin "2") (pinfunction "2_2") (pintype "passive"))
    )
    (net (code "16") (name "DC+") (class "Default")
      (node (ref "C1") (pin "2") (pinfunction "2_2") (pintype "passive"))
      (node (ref "L1") (pin "1") (pinfunction "1_1") (pintype "passive"))
      (node (ref "R1") (pin "2") (pinfunction "2_2") (pintype "passive"))
      (node (ref "X1") (pin "1") (pinfunction "1_1") (pintype "passive"))
    )
    (net (code "17") (name "DC-") (class "Default")
      (node (ref "C1") (pin "1") (pinfunction "1_1") (pintype "passive"))
      (node (ref "L1") (pin "3") (pinfunction "1_3") (pintype "passive"))
      (node (ref "R1") (pin "1") (pinfunction "1_1") (pintype "passive"))
      (node (ref "X1") (pin "2") (pinfunction "1_2") (pintype "passive"))
    )
    (net (code "18") (name "DC_OUT") (class "Default")
      (node (ref "C2") (pin "+") (pinfunction "+_+") (pintype "passive"))
      (node (ref "C22") (pin "1") (pinfunction "1_1") (pintype "passive"))
      (node (ref "C23") (pin "1") (pinfunction "1_1") (pintype "passive"))
      (node (ref "C4") (pin "2") (pinfunction "2_2") (pintype "passive"))
      (node (ref "C5") (pin "1") (pinfunction "1_1") (pintype "passive"))
      (node (ref "C6") (pin "1") (pinfunction "1_1") (pintype "passive"))
      (node (ref "C7") (pin "1") (pinfunction "1_1") (pintype "passive"))
      (node (ref "C8") (pin "2") (pinfunction "2_2") (pintype "passive"))
      (node (ref "IC1") (pin "11") (pinfunction "VIN_11") (pintype "passive"))
      (node (ref "IC2") (pin "2") (pinfunction "VIN_2") (pintype "power_in"))
      (node (ref "L1") (pin "2") (pinfunction "2_2") (pintype "passive"))
      (node (ref "R13") (pin "2") (pinfunction "2_2") (pintype "passive"))
      (node (ref "R3") (pin "1") (pinfunction "1_1") (pintype "passive"))
      (node (ref "ZD1") (pin "C") (pinfunction "C_C") (pintype "passive"))
    )
    (net (code "19") (name "DIB_A0") (class "Default")
      (node (ref "IC8") (pin "1") (pinfunction "A0_1") (pintype "input"))
      (node (ref "R24") (pin "2") (pinfunction "2_2") (pintype "passive"))
      (node (ref "X2") (pin "17") (pinfunction "1_17") (pintype "passive"))
    )
    (net (code "20") (name "DIB_A1") (class "Default")
      (node (ref "IC8") (pin "2") (pinfunction "A1_2") (pintype "input"))
      (node (ref "R23") (pin "2") (pinfunction "2_2") (pintype "passive"))
      (node (ref "X2") (pin "19") (pinfunction "1_19") (pintype "passive"))
    )
    (net (code "21") (name "DIB_A2") (class "Default")
      (node (ref "IC8") (pin "3") (pinfunction "A2_3") (pintype "input"))
      (node (ref "R22") (pin "2") (pinfunction "2_2") (pintype "passive"))
      (node (ref "X2") (pin "18") (pinfunction "1_18") (pintype "passive"))
    )
    (net (code "22") (name "DIB_CSA") (class "Default")
      (node (ref "IC3") (pin "4") (pinfunction "A2_4") (pintype "input"))
      (node (ref "X2") (pin "9") (pinfunction "1_9") (pintype "passive"))
    )
    (net (code "23") (name "DIB_CSB") (class "Default")
      (node (ref "IC3") (pin "5") (pinfunction "A3_5") (pintype "input"))
      (node (ref "X2") (pin "12") (pinfunction "1_12") (pintype "passive"))
    )
    (net (code "24") (name "DIB_IRQ") (class "Default")
      (node (ref "IC7") (pin "6") (pinfunction "A4_6") (pintype "output"))
      (node (ref "X2") (pin "10") (pinfunction "1_10") (pintype "passive"))
    )
    (net (code "25") (name "DIB_MISO") (class "Default")
      (node (ref "IC3") (pin "6") (pinfunction "A4_6") (pintype "output"))
      (node (ref "X2") (pin "14") (pinfunction "1_14") (pintype "passive"))
    )
    (net (code "26") (name "DIB_MOSI") (class "Default")
      (node (ref "IC7") (pin "3") (pinfunction "A1_3") (pintype "input"))
      (node (ref "X2") (pin "15") (pinfunction "1_15") (pintype "passive"))
    )
    (net (code "27") (name "DIB_NRESET") (class "Default")
      (node (ref "IC7") (pin "5") (pinfunction "A3_5") (pintype "input"))
      (node (ref "X2") (pin "4") (pinfunction "1_4") (pintype "passive"))
    )
    (net (code "28") (name "DIB_SCL") (class "Default")
      (node (ref "IC8") (pin "6") (pinfunction "SCL_6") (pintype "bidirectional"))
      (node (ref "X2") (pin "5") (pinfunction "1_5") (pintype "passive"))
    )
    (net (code "29") (name "DIB_SCLK") (class "Default")
      (node (ref "IC3") (pin "3") (pinfunction "A1_3") (pintype "input"))
      (node (ref "X2") (pin "13") (pinfunction "1_13") (pintype "passive"))
    )
    (net (code "30") (name "DIB_SDA") (class "Default")
      (node (ref "IC8") (pin "5") (pinfunction "SDA_5") (pintype "bidirectional"))
      (node (ref "X2") (pin "8") (pinfunction "1_8") (pintype "passive"))
    )
    (net (code "31") (name "FB") (class "Default")
      (node (ref "C19") (pin "1") (pinfunction "1_1") (pintype "passive"))
      (node (ref "IC1") (pin "5") (pinfunction "VFB_5") (pintype "input"))
      (node (ref "Q2") (pin "C") (pinfunction "C_C") (pintype "passive"))
      (node (ref "R11") (pin "1") (pinfunction "1_1") (pintype "passive"))
      (node (ref "R9") (pin "2") (pinfunction "2_2") (pintype "passive"))
    )
    (net (code "32") (name "GCOM") (class "Default")
      (node (ref "IC10") (pin "6") (pinfunction "-IN_6") (pintype "input"))
      (node (ref "IC10") (pin "7") (pinfunction "OUT_7") (pintype "output"))
      (node (ref "R39") (pin "1") (pinfunction "1_1") (pintype "passive"))
      (node (ref "R52") (pin "1") (pinfunction "1_1") (pintype "passive"))
    )
    (net (code "33") (name "GND") (class "Default")
      (node (ref "C20") (pin "2") (pinfunction "2_2") (pintype "passive"))
      (node (ref "C21") (pin "2") (pinfunction "2_2") (pintype "passive"))
      (node (ref "C22") (pin "2") (pinfunction "2_2") (pintype "passive"))
      (node (ref "C23") (pin "2") (pinfunction "2_2") (pintype "passive"))
      (node (ref "C26") (pin "2") (pinfunction "2_2") (pintype "passive"))
      (node (ref "C27") (pin "2") (pinfunction "2_2") (pintype "passive"))
      (node (ref "C28") (pin "2") (pinfunction "2_2") (pintype "passive"))
      (node (ref "C29") (pin "1") (pinfunction "1_1") (pintype "passive"))
      (node (ref "C31") (pin "1") (pinfunction "1_1") (pintype "passive"))
      (node (ref "C32") (pin "2") (pinfunction "2_2") (pintype "passive"))
      (node (ref "C33") (pin "1") (pinfunction "1_1") (pintype "passive"))
      (node (ref "C34") (pin "2") (pinfunction "2_2") (pintype "passive"))
      (node (ref "C36") (pin "1") (pinfunction "1_1") (pintype "passive"))
      (node (ref "C37") (pin "1") (pinfunction "1_1") (pintype "passive"))
      (node (ref "C39") (pin "2") (pinfunction "2_2") (pintype "passive"))
      (node (ref "C46") (pin "1") (pinfunction "1_1") (pintype "passive"))
      (node (ref "C47") (pin "2") (pinfunction "2_2") (pintype "passive"))
      (node (ref "C48") (pin "1") (pinfunction "1_1") (pintype "passive"))
      (node (ref "C49") (pin "1") (pinfunction "1_1") (pintype "passive"))
      (node (ref "C50") (pin "1") (pinfunction "1_1") (pintype "passive"))
      (node (ref "C51") (pin "1") (pinfunction "1_1") (pintype "passive"))
      (node (ref "C53") (pin "1") (pinfunction "1_1") (pintype "passive"))
      (node (ref "C54") (pin "2") (pinfunction "2_2") (pintype "passive"))
      (node (ref "C55") (pin "1") (pinfunction "1_1") (pintype "passive"))
      (node (ref "C56") (pin "1") (pinfunction "1_1") (pintype "passive"))
      (node (ref "C62") (pin "1") (pinfunction "1_1") (pintype "passive"))
      (node (ref "C63") (pin "2") (pinfunction "2_2") (pintype "passive"))
      (node (ref "C64") (pin "2") (pinfunction "2_2") (pintype "passive"))
      (node (ref "C65") (pin "2") (pinfunction "2_2") (pintype "passive"))
      (node (ref "C66") (pin "-") (pinfunction "-_-") (pintype "passive"))
      (node (ref "C67") (pin "2") (pinfunction "2_2") (pintype "passive"))
      (node (ref "C68") (pin "2") (pinfunction "2_2") (pintype "passive"))
      (node (ref "C69") (pin "1") (pinfunction "1_1") (pintype "passive"))
      (node (ref "C70") (pin "1") (pinfunction "1_1") (pintype "passive"))
      (node (ref "C71") (pin "2") (pinfunction "2_2") (pintype "passive"))
      (node (ref "C72") (pin "1") (pinfunction "1_1") (pintype "passive"))
      (node (ref "C73") (pin "1") (pinfunction "1_1") (pintype "passive"))
      (node (ref "C74") (pin "1") (pinfunction "1_1") (pintype "passive"))
      (node (ref "C75") (pin "2") (pinfunction "2_2") (pintype "passive"))
      (node (ref "C76") (pin "1") (pinfunction "1_1") (pintype "passive"))
      (node (ref "C77") (pin "1") (pinfunction "1_1") (pintype "passive"))
      (node (ref "C78") (pin "1") (pinfunction "1_1") (pintype "passive"))
      (node (ref "C79") (pin "1") (pinfunction "1_1") (pintype "passive"))
      (node (ref "C80") (pin "1") (pinfunction "1_1") (pintype "passive"))
      (node (ref "C81") (pin "1") (pinfunction "1_1") (pintype "passive"))
      (node (ref "C82") (pin "2") (pinfunction "2_2") (pintype "passive"))
      (node (ref "C83") (pin "1") (pinfunction "1_1") (pintype "passive"))
      (node (ref "C84") (pin "1") (pinfunction "1_1") (pintype "passive"))
      (node (ref "C85") (pin "1") (pinfunction "1_1") (pintype "passive"))
      (node (ref "C86") (pin "1") (pinfunction "1_1") (pintype "passive"))
      (node (ref "C87") (pin "1") (pinfunction "1_1") (pintype "passive"))
      (node (ref "D10") (pin "C") (pinfunction "C_C") (pintype "passive"))
      (node (ref "D17") (pin "C") (pinfunction "C_C") (pintype "passive"))
      (node (ref "D5") (pin "A") (pinfunction "A_A") (pintype "passive"))
      (node (ref "D6") (pin "A") (pinfunction "A_A") (pintype "passive"))
      (node (ref "D7") (pin "C") (pinfunction "C_C") (pintype "passive"))
      (node (ref "D9") (pin "C") (pinfunction "C_C") (pintype "passive"))
      (node (ref "GND") (pin "1") (pinfunction "P$1_1") (pintype "bidirectional"))
      (node (ref "IC12") (pin "4") (pinfunction "VSS_4") (pintype "power_in"))
      (node (ref "IC13") (pin "10") (pinfunction "VSS_10") (pintype "power_in"))
      (node (ref "IC13") (pin "15") (pinfunction "A0_15") (pintype "input"))
      (node (ref "IC13") (pin "16") (pinfunction "A1_16") (pintype "input"))
      (node (ref "IC13") (pin "17") (pinfunction "A2_17") (pintype "input"))
      (node (ref "IC14") (pin "4") (pinfunction "GND_4") (pintype "passive"))
      (node (ref "IC15") (pin "2") (pinfunction "GND_2") (pintype "passive"))
      (node (ref "IC16") (pin "8") (pinfunction "GND_8") (pintype "power_in"))
      (node (ref "IC17") (pin "2") (pinfunction "GND_2") (pintype "passive"))
      (node (ref "IC18") (pin "3") (pinfunction "CLK_3") (pintype "bidirectional"))
      (node (ref "IC18") (pin "4") (pinfunction "DGND_4") (pintype "passive"))
      (node (ref "IC18") (pin "5") (pinfunction "AVSS_5") (pintype "passive"))
      (node (ref "IC18") (pin "8") (pinfunction "REFN0_8") (pintype "input"))
      (node (ref "IC2") (pin "9") (pinfunction "GND_9") (pintype "passive"))
      (node (ref "IC2") (pin "TP") (pinfunction "TP_TP") (pintype "passive"))
      (node (ref "IC20") (pin "4") (pinfunction "GND_4") (pintype "passive"))
      (node (ref "IC3") (pin "15") (pinfunction "GND2_15") (pintype "passive"))
      (node (ref "IC3") (pin "9") (pinfunction "GND2_2_9") (pintype "passive"))
      (node (ref "IC4") (pin "4") (pinfunction "GND_4") (pintype "passive"))
      (node (ref "IC5") (pin "2") (pinfunction "GND_2") (pintype "passive"))
      (node (ref "IC5") (pin "3") (pinfunction "GND_3") (pintype "passive"))
      (node (ref "IC5") (pin "6") (pinfunction "GND_6") (pintype "passive"))
      (node (ref "IC5") (pin "7") (pinfunction "GND_7") (pintype "passive"))
      (node (ref "IC6") (pin "5") (pinfunction "GND_5") (pintype "passive"))
      (node (ref "IC7") (pin "15") (pinfunction "GND2_15") (pintype "passive"))
      (node (ref "IC7") (pin "9") (pinfunction "GND2_2_9") (pintype "passive"))
      (node (ref "KK3") (pin "1") (pinfunction "1_1") (pintype "passive"))
      (node (ref "KK3") (pin "2") (pinfunction "2_2") (pintype "passive"))
      (node (ref "Q15") (pin "2") (pinfunction "S_2") (pintype "passive"))
      (node (ref "Q16") (pin "2") (pinfunction "S_2") (pintype "passive"))
      (node (ref "Q17") (pin "2") (pinfunction "S_2") (pintype "passive"))
      (node (ref "Q19") (pin "E") (pinfunction "E_E") (pintype "passive"))
      (node (ref "Q21") (pin "2") (pinfunction "S_2") (pintype "passive"))
      (node (ref "Q9") (pin "2") (pinfunction "S_2") (pintype "passive"))
      (node (ref "R103") (pin "1") (pinfunction "1_1") (pintype "passive"))
      (node (ref "R106") (pin "1") (pinfunction "1_1") (pintype "passive"))
      (node (ref "R15") (pin "1") (pinfunction "1_1") (pintype "passive"))
      (node (ref "R16") (pin "1") (pinfunction "1_1") (pintype "passive"))
      (node (ref "R19") (pin "1") (pinfunction "1_1") (pintype "passive"))
      (node (ref "R21") (pin "1") (pinfunction "1_1") (pintype "passive"))
      (node (ref "R36") (pin "2") (pinfunction "2_2") (pintype "passive"))
      (node (ref "R51") (pin "1") (pinfunction "1_1") (pintype "passive"))
      (node (ref "R54") (pin "1") (pinfunction "1_1") (pintype "passive"))
      (node (ref "R60") (pin "1") (pinfunction "1_1") (pintype "passive"))
      (node (ref "R68") (pin "2") (pinfunction "2_2") (pintype "passive"))
      (node (ref "R74") (pin "1") (pinfunction "1_1") (pintype "passive"))
      (node (ref "R83") (pin "2") (pinfunction "2_2") (pintype "passive"))
      (node (ref "R90") (pin "1") (pinfunction "1_1") (pintype "passive"))
      (node (ref "R91") (pin "1") (pinfunction "1_1") (pintype "passive"))
      (node (ref "SH1") (pin "2") (pinfunction "GND_B_2") (pintype "bidirectional"))
      (node (ref "TR1") (pin "4") (pinfunction "4_4") (pintype "passive"))
      (node (ref "X3") (pin "2") (pinfunction "1_2") (pintype "passive"))
      (node (ref "ZD3") (pin "1") (pinfunction "A_1") (pintype "passive"))
      (node (ref "ZD3") (pin "2") (pinfunction "A_2") (pintype "passive"))
    )
    (net (code "34") (name "GNDIO") (class "Default")
      (node (ref "C30") (pin "2") (pinfunction "2_2") (pintype "passive"))
      (node (ref "C35") (pin "2") (pinfunction "2_2") (pintype "passive"))
      (node (ref "C38") (pin "1") (pinfunction "1_1") (pintype "passive"))
      (node (ref "IC3") (pin "2") (pinfunction "GND1_2_2") (pintype "passive"))
      (node (ref "IC3") (pin "8") (pinfunction "GND1_8") (pintype "passive"))
      (node (ref "IC7") (pin "2") (pinfunction "GND1_2_2") (pintype "passive"))
      (node (ref "IC7") (pin "8") (pinfunction "GND1_8") (pintype "passive"))
      (node (ref "IC8") (pin "4") (pinfunction "GND_4") (pintype "passive"))
      (node (ref "IC8") (pin "7") (pinfunction "WP_7") (pintype "input"))
      (node (ref "X2") (pin "11") (pinfunction "1_11") (pintype "passive"))
      (node (ref "X2") (pin "16") (pinfunction "1_16") (pintype "passive"))
      (node (ref "X2") (pin "20") (pinfunction "1_20") (pintype "passive"))
      (node (ref "X2") (pin "25") (pinfunction "1_25") (pintype "passive"))
      (node (ref "X2") (pin "7") (pinfunction "1_7") (pintype "passive"))
    )
    (net (code "35") (name "IRQ") (class "Default")
      (node (ref "IC13") (pin "20") (pinfunction "INTA_20") (pintype "output"))
      (node (ref "IC7") (pin "11") (pinfunction "B4_11") (pintype "input"))
    )
    (net (code "36") (name "ISENSE+") (class "Default")
      (node (ref "IC11") (pin "3") (pinfunction "+IN_3") (pintype "input"))
      (node (ref "R52") (pin "2") (pinfunction "2_2") (pintype "passive"))
      (node (ref "R53") (pin "2") (pinfunction "2_2") (pintype "passive"))
    )
    (net (code "37") (name "ISENSE-") (class "Default")
      (node (ref "C58") (pin "1") (pinfunction "1_1") (pintype "passive"))
      (node (ref "IC11") (pin "2") (pinfunction "-IN_2") (pintype "input"))
      (node (ref "R59") (pin "1") (pinfunction "1_1") (pintype "passive"))
      (node (ref "R63") (pin "2") (pinfunction "2_2") (pintype "passive"))
    )
    (net (code "38") (name "I_MON") (class "Default")
      (node (ref "C58") (pin "2") (pinfunction "2_2") (pintype "passive"))
      (node (ref "IC11") (pin "6") (pinfunction "OUT_6") (pintype "output"))
      (node (ref "R57") (pin "1") (pinfunction "1_1") (pintype "passive"))
      (node (ref "R59") (pin "2") (pinfunction "2_2") (pintype "passive"))
      (node (ref "R76") (pin "1") (pinfunction "1_1") (pintype "passive"))
    )
    (net (code "39") (name "I_SERVO") (class "Default")
      (node (ref "C52") (pin "2") (pinfunction "2_2") (pintype "passive"))
      (node (ref "C57") (pin "2") (pinfunction "2_2") (pintype "passive"))
      (node (ref "D12") (pin "C") (pinfunction "C_C") (pintype "passive"))
      (node (ref "IC10") (pin "1") (pinfunction "OUT_1") (pintype "output"))
      (node (ref "R93") (pin "1") (pinfunction "1_1") (pintype "passive"))
    )
    (net (code "40") (name "I_SET") (class "Default")
      (node (ref "I_SET") (pin "2") (pinfunction "2_2") (pintype "passive"))
      (node (ref "R55") (pin "1") (pinfunction "1_1") (pintype "passive"))
      (node (ref "R72") (pin "1") (pinfunction "1_1") (pintype "passive"))
    )
    (net (code "41") (name "LOOP_CTRL") (class "Default")
      (node (ref "D11") (pin "A") (pinfunction "A_A") (pintype "passive"))
      (node (ref "D12") (pin "A") (pinfunction "A_A") (pintype "passive"))
      (node (ref "Q8") (pin "1") (pinfunction "B_1") (pintype "passive"))
      (node (ref "R40") (pin "1") (pinfunction "1_1") (pintype "passive"))
      (node (ref "R89") (pin "2") (pinfunction "2_2") (pintype "passive"))
    )
    (net (code "42") (name "MISO") (class "Default")
      (node (ref "IC13") (pin "14") (pinfunction "SO_14") (pintype "output"))
      (node (ref "IC15") (pin "4") (pinfunction "SI/O_4") (pintype "bidirectional"))
      (node (ref "IC18") (pin "15") (pinfunction "DOUT/~{DRDY}_15") (pintype "output"))
      (node (ref "RN2") (pin "7") (pinfunction "2_7") (pintype "passive"))
    )
    (net (code "43") (name "MOSI") (class "Default")
      (node (ref "IC13") (pin "13") (pinfunction "SI_13") (pintype "input"))
      (node (ref "IC16") (pin "7") (pinfunction "DIN_7") (pintype "input"))
      (node (ref "IC18") (pin "16") (pinfunction "DIN_16") (pintype "input"))
      (node (ref "RN2") (pin "6") (pinfunction "2_6") (pintype "passive"))
    )
    (net (code "44") (name "Net-(C10-Pad1)") (class "Default")
      (node (ref "C10") (pin "1") (pinfunction "1_1") (pintype "passive"))
      (node (ref "C11") (pin "+") (pinfunction "+_+") (pintype "passive"))
      (node (ref "C15") (pin "1") (pinfunction "1_1") (pintype "passive"))
      (node (ref "C16") (pin "+") (pinfunction "+_+") (pintype "passive"))
      (node (ref "L2") (pin "2") (pinfunction "2_2") (pintype "passive"))
      (node (ref "L3") (pin "1") (pinfunction "1_1") (pintype "passive"))
      (node (ref "R4") (pin "1") (pinfunction "1_1") (pintype "passive"))
      (node (ref "R6") (pin "1") (pinfunction "1_1") (pintype "passive"))
      (node (ref "R7") (pin "1") (pinfunction "1_1") (pintype "passive"))
      (node (ref "R9") (pin "1") (pinfunction "1_1") (pintype "passive"))
    )
    (net (code "45") (name "Net-(C12-Pad2)") (class "Default")
      (node (ref "C12") (pin "2") (pinfunction "2_2") (pintype "passive"))
      (node (ref "R5") (pin "2") (pinfunction "2_2") (pintype "passive"))
    )
    (net (code "46") (name "Net-(C18-Pad1)") (class "Default")
      (node (ref "C18") (pin "1") (pinfunction "1_1") (pintype "passive"))
      (node (ref "R8") (pin "1") (pinfunction "1_1") (pintype "passive"))
    )
    (net (code "47") (name "Net-(C19-Pad2)") (class "Default")
      (node (ref "C19") (pin "2") (pinfunction "2_2") (pintype "passive"))
      (node (ref "D3") (pin "A") (pinfunction "A_A") (pintype "passive"))
      (node (ref "Q2") (pin "B") (pinfunction "B_B") (pintype "passive"))
      (node (ref "R10") (pin "1") (pinfunction "1_1") (pintype "passive"))
      (node (ref "R7") (pin "2") (pinfunction "2_2") (pintype "passive"))
    )
    (net (code "48") (name "Net-(C20-Pad1)") (class "Default")
      (node (ref "C20") (pin "1") (pinfunction "1_1") (pintype "passive"))
      (node (ref "D4") (pin "A") (pinfunction "A_A") (pintype "passive"))
      (node (ref "R12") (pin "2") (pinfunction "2_2") (pintype "passive"))
    )
    (net (code "49") (name "Net-(C25-Pad2)") (class "Default")
      (node (ref "C25") (pin "2") (pinfunction "2_2") (pintype "passive"))
      (node (ref "R15") (pin "2") (pinfunction "2_2") (pintype "passive"))
    )
    (net (code "50") (name "Net-(C26-Pad1)") (class "Default")
      (node (ref "C26") (pin "1") (pinfunction "1_1") (pintype "passive"))
      (node (ref "R14") (pin "2") (pinfunction "2_2") (pintype "passive"))
      (node (ref "R18") (pin "2") (pinfunction "2_2") (pintype "passive"))
      (node (ref "TR1") (pin "3") (pinfunction "3_3") (pintype "passive"))
    )
    (net (code "51") (name "Net-(C33-Pad2)") (class "Default")
      (node (ref "C33") (pin "2") (pinfunction "2_2") (pintype "passive"))
      (node (ref "R20") (pin "1") (pinfunction "1_1") (pintype "passive"))
    )
    (net (code "52") (name "Net-(C40-Pad1)") (class "Default")
      (node (ref "C40") (pin "1") (pinfunction "1_1") (pintype "passive"))
      (node (ref "D10") (pin "A") (pinfunction "A_A") (pintype "passive"))
      (node (ref "Q7") (pin "B") (pinfunction "B_B") (pintype "passive"))
      (node (ref "R41") (pin "2") (pinfunction "2_2") (pintype "passive"))
    )
    (net (code "53") (name "Net-(C40-Pad2)") (class "Default")
      (node (ref "C40") (pin "2") (pinfunction "2_2") (pintype "passive"))
      (node (ref "Q7") (pin "C") (pinfunction "C_C") (pintype "passive"))
      (node (ref "R35") (pin "2") (pinfunction "2_2") (pintype "passive"))
    )
    (net (code "54") (name "Net-(C41-Pad2)") (class "Default")
      (node (ref "C41") (pin "2") (pinfunction "2_2") (pintype "passive"))
      (node (ref "R42") (pin "1") (pinfunction "1_1") (pintype "passive"))
    )
    (net (code "55") (name "Net-(C43-Pad1)") (class "Default")
      (node (ref "C43") (pin "1") (pinfunction "1_1") (pintype "passive"))
      (node (ref "R49") (pin "2") (pinfunction "2_2") (pintype "passive"))
    )
    (net (code "56") (name "Net-(C44-Pad2)") (class "Default")
      (node (ref "C44") (pin "2") (pinfunction "2_2") (pintype "passive"))
      (node (ref "R50") (pin "1") (pinfunction "1_1") (pintype "passive"))
    )
    (net (code "57") (name "Net-(C52-Pad1)") (class "Default")
      (node (ref "C52") (pin "1") (pinfunction "1_1") (pintype "passive"))
      (node (ref "R58") (pin "1") (pinfunction "1_1") (pintype "passive"))
    )
    (net (code "58") (name "Net-(C59-Pad2)") (class "Default")
      (node (ref "C59") (pin "2") (pinfunction "2_2") (pintype "passive"))
      (node (ref "R62") (pin "1") (pinfunction "1_1") (pintype "passive"))
    )
    (net (code "59") (name "Net-(C88-Pad2)") (class "Default")
      (node (ref "C88") (pin "2") (pinfunction "2_2") (pintype "passive"))
      (node (ref "Q18") (pin "B") (pinfunction "B_B") (pintype "passive"))
      (node (ref "R95") (pin "1") (pinfunction "1_1") (pintype "passive"))
      (node (ref "R96") (pin "2") (pinfunction "2_2") (pintype "passive"))
      (node (ref "R98") (pin "2") (pinfunction "2_2") (pintype "passive"))
    )
    (net (code "60") (name "Net-(C89-Pad2)") (class "Default")
      (node (ref "C89") (pin "2") (pinfunction "2_2") (pintype "passive"))
      (node (ref "R101") (pin "2") (pinfunction "2_2") (pintype "passive"))
    )
    (net (code "61") (name "Net-(C96-Pad1)") (class "Default")
      (node (ref "C96") (pin "1") (pinfunction "1_1") (pintype "passive"))
      (node (ref "Q20") (pin "B") (pinfunction "B_B") (pintype "passive"))
      (node (ref "R102") (pin "1") (pinfunction "1_1") (pintype "passive"))
      (node (ref "R104") (pin "2") (pinfunction "2_2") (pintype "passive"))
    )
    (net (code "62") (name "Net-(D2-C)") (class "Default")
      (node (ref "C12") (pin "1") (pinfunction "1_1") (pintype "passive"))
      (node (ref "D2") (pin "3") (pinfunction "C_3") (pintype "passive"))
      (node (ref "L2") (pin "1") (pinfunction "1_1") (pintype "passive"))
      (node (ref "Q1") (pin "2") (pinfunction "D_2") (pintype "passive"))
    )
    (net (code "63") (name "Net-(D3-PadC)") (class "Default")
      (node (ref "D3") (pin "C") (pinfunction "C_C") (pintype "passive"))
      (node (ref "Q2") (pin "E") (pinfunction "E_E") (pintype "passive"))
      (node (ref "R6") (pin "2") (pinfunction "2_2") (pintype "passive"))
    )
    (net (code "64") (name "Net-(D4-PadC)") (class "Default")
      (node (ref "D4") (pin "C") (pinfunction "C_C") (pintype "passive"))
      (node (ref "TR1") (pin "2") (pinfunction "2_2") (pintype "passive"))
    )
    (net (code "65") (name "Net-(D16-PadA)") (class "Default")
      (node (ref "D16") (pin "A") (pinfunction "A_A") (pintype "passive"))
      (node (ref "Q14") (pin "B") (pinfunction "B_B") (pintype "passive"))
      (node (ref "R85") (pin "1") (pinfunction "1_1") (pintype "passive"))
      (node (ref "R90") (pin "2") (pinfunction "2_2") (pintype "passive"))
    )
    (net (code "66") (name "Net-(D16-PadC)") (class "Default")
      (node (ref "D16") (pin "C") (pinfunction "C_C") (pintype "passive"))
      (node (ref "D17") (pin "A") (pinfunction "A_A") (pintype "passive"))
    )
    (net (code "67") (name "Net-(D18-C)") (class "Default")
      (node (ref "C88") (pin "1") (pinfunction "1_1") (pintype "passive"))
      (node (ref "C89") (pin "1") (pinfunction "1_1") (pintype "passive"))
      (node (ref "C90") (pin "+") (pinfunction "+_+") (pintype "passive"))
      (node (ref "D18") (pin "3") (pinfunction "C_3") (pintype "passive"))
      (node (ref "F1") (pin "2") (pinfunction "2_2") (pintype "passive"))
      (node (ref "F2") (pin "1") (pinfunction "1_1") (pintype "passive"))
      (node (ref "JP3") (pin "2") (pinfunction "2_2") (pintype "passive"))
      (node (ref "K1") (pin "2") (pinfunction "O_2") (pintype "passive"))
      (node (ref "Q18") (pin "E") (pinfunction "E_E") (pintype "passive"))
      (node (ref "R95") (pin "2") (pinfunction "2_2") (pintype "passive"))
    )
    (net (code "68") (name "Net-(FB1-1)") (class "Default")
      (node (ref "C34") (pin "1") (pinfunction "1_1") (pintype "passive"))
      (node (ref "D6") (pin "C") (pinfunction "C_C") (pintype "passive"))
      (node (ref "FB1") (pin "P$1") (pinfunction "1_P$1") (pintype "passive"))
      (node (ref "FB2") (pin "P$1") (pinfunction "1_P$1") (pintype "passive"))
      (node (ref "IC5") (pin "1") (pinfunction "VO_1") (pintype "passive"))
    )
    (net (code "69") (name "Net-(FB3-1)") (class "Default")
      (node (ref "C37") (pin "2") (pinfunction "2_2") (pintype "passive"))
      (node (ref "D7") (pin "A") (pinfunction "A_A") (pintype "passive"))
      (node (ref "FB3") (pin "P$1") (pinfunction "1_P$1") (pintype "passive"))
      (node (ref "IC6") (pin "1") (pinfunction "OUT_1") (pintype "passive"))
    )
    (net (code "70") (name "Net-(IC1-CAP)") (class "Default")
      (node (ref "C8") (pin "1") (pinfunction "1_1") (pintype "passive"))
      (node (ref "IC1") (pin "9") (pinfunction "CAP_9") (pintype "passive"))
    )
    (net (code "71") (name "Net-(IC1-GATE)") (class "Default")
      (node (ref "IC1") (pin "12") (pinfunction "GATE_12") (pintype "output"))
      (node (ref "Q1") (pin "1") (pinfunction "G_1") (pintype "passive"))
    )
    (net (code "72") (name "Net-(IC1-ITH)") (class "Default")
      (node (ref "C17") (pin "1") (pinfunction "1_1") (pintype "passive"))
      (node (ref "IC1") (pin "6") (pinfunction "ITH_6") (pintype "bidirectional"))
      (node (ref "R8") (pin "2") (pinfunction "2_2") (pintype "passive"))
    )
    (net (code "73") (name "Net-(IC1-RUN)") (class "Default")
      (node (ref "D1") (pin "C") (pinfunction "C_C") (pintype "passive"))
      (node (ref "IC1") (pin "8") (pinfunction "RUN_8") (pintype "input"))
      (node (ref "R2") (pin "2") (pinfunction "2_2") (pintype "passive"))
    )
    (net (code "74") (name "Net-(IC1-SENSE)") (class "Default")
      (node (ref "IC1") (pin "10") (pinfunction "SENSE_10") (pintype "input"))
      (node (ref "Q1") (pin "3") (pinfunction "S_3") (pintype "passive"))
      (node (ref "R3") (pin "2") (pinfunction "2_2") (pintype "passive"))
    )
    (net (code "75") (name "Net-(IC1-SS)") (class "Default")
      (node (ref "C9") (pin "2") (pinfunction "2_2") (pintype "passive"))
      (node (ref "IC1") (pin "4") (pinfunction "SS_4") (pintype "input"))
    )
    (net (code "76") (name "Net-(IC2-BOOT)") (class "Default")
      (node (ref "C24") (pin "2") (pinfunction "2_2") (pintype "passive"))
      (node (ref "IC2") (pin "1") (pinfunction "BOOT_1") (pintype "output"))
    )
    (net (code "77") (name "Net-(IC2-COMP)") (class "Default")
      (node (ref "C29") (pin "2") (pinfunction "2_2") (pintype "passive"))
      (node (ref "IC2") (pin "8") (pinfunction "COMP_8") (pintype "output"))
      (node (ref "R20") (pin "2") (pinfunction "2_2") (pintype "passive"))
    )
    (net (code "78") (name "Net-(IC2-EN)") (class "Default")
      (node (ref "IC2") (pin "3") (pinfunction "EN_3") (pintype "input"))
      (node (ref "R13") (pin "1") (pinfunction "1_1") (pintype "passive"))
      (node (ref "R16") (pin "2") (pinfunction "2_2") (pintype "passive"))
    )
    (net (code "79") (name "Net-(IC2-PH)") (class "Default")
      (node (ref "C24") (pin "1") (pinfunction "1_1") (pintype "passive"))
      (node (ref "C25") (pin "1") (pinfunction "1_1") (pintype "passive"))
      (node (ref "D5") (pin "C") (pinfunction "C_C") (pintype "passive"))
      (node (ref "IC2") (pin "10") (pinfunction "PH_10") (pintype "input"))
      (node (ref "TR1") (pin "1") (pinfunction "1_1") (pintype "passive"))
    )
    (net (code "80") (name "Net-(IC2-RT{slash}CLK)") (class "Default")
      (node (ref "IC2") (pin "5") (pinfunction "RT/CLK_5") (pintype "input"))
      (node (ref "R19") (pin "2") (pinfunction "2_2") (pintype "passive"))
    )
    (net (code "81") (name "Net-(IC2-SS{slash}TR)") (class "Default")
      (node (ref "C28") (pin "1") (pinfunction "1_1") (pintype "passive"))
      (node (ref "IC2") (pin "4") (pinfunction "SS/TR_4") (pintype "input"))
    )
    (net (code "82") (name "Net-(IC2-VSENSE)") (class "Default")
      (node (ref "IC2") (pin "7") (pinfunction "VSENSE_7") (pintype "input"))
      (node (ref "R18") (pin "1") (pinfunction "1_1") (pintype "passive"))
      (node (ref "R21") (pin "2") (pinfunction "2_2") (pintype "passive"))
    )
    (net (code "83") (name "Net-(IC3-B1)") (class "Default")
      (node (ref "IC3") (pin "14") (pinfunction "B1_14") (pintype "output"))
      (node (ref "RN2") (pin "1") (pinfunction "1_1") (pintype "passive"))
    )
    (net (code "84") (name "Net-(IC3-B4)") (class "Default")
      (node (ref "IC3") (pin "11") (pinfunction "B4_11") (pintype "input"))
      (node (ref "RN2") (pin "2") (pinfunction "1_2") (pintype "passive"))
    )
    (net (code "85") (name "Net-(IC4-Y0)") (class "Default")
      (node (ref "IC4") (pin "7") (pinfunction "Y0_7") (pintype "output"))
      (node (ref "RN1") (pin "1") (pinfunction "1_1") (pintype "passive"))
    )
    (net (code "86") (name "Net-(IC4-Y1)") (class "Default")
      (node (ref "IC4") (pin "6") (pinfunction "Y1_6") (pintype "output"))
      (node (ref "RN1") (pin "2") (pinfunction "1_2") (pintype "passive"))
    )
    (net (code "87") (name "Net-(IC4-Y2)") (class "Default")
      (node (ref "IC4") (pin "5") (pinfunction "Y2_5") (pintype "output"))
      (node (ref "RN1") (pin "3") (pinfunction "1_3") (pintype "passive"))
    )
    (net (code "88") (name "Net-(IC4-Y3)") (class "Default")
      (node (ref "IC4") (pin "3") (pinfunction "Y3_3") (pintype "output"))
      (node (ref "RN1") (pin "4") (pinfunction "1_4") (pintype "passive"))
    )
    (net (code "89") (name "Net-(IC7-B1)") (class "Default")
      (node (ref "IC7") (pin "14") (pinfunction "B1_14") (pintype "output"))
      (node (ref "RN2") (pin "3") (pinfunction "1_3") (pintype "passive"))
    )
    (net (code "90") (name "Net-(IC7-B2)") (class "Default")
      (node (ref "IC7") (pin "13") (pinfunction "B2_13") (pintype "output"))
      (node (ref "RN2") (pin "4") (pinfunction "1_4") (pintype "passive"))
    )
    (net (code "91") (name "Net-(IC9A-+IN)") (class "Default")
      (node (ref "IC9") (pin "3") (pinfunction "+IN_3") (pintype "input"))
      (node (ref "R42") (pin "2") (pinfunction "2_2") (pintype "passive"))
      (node (ref "R45") (pin "2") (pinfunction "2_2") (pintype "passive"))
    )
    (net (code "92") (name "Net-(IC9A--IN)") (class "Default")
      (node (ref "C45") (pin "1") (pinfunction "1_1") (pintype "passive"))
      (node (ref "IC9") (pin "2") (pinfunction "-IN_2") (pintype "input"))
      (node (ref "R46") (pin "2") (pinfunction "2_2") (pintype "passive"))
      (node (ref "R49") (pin "1") (pinfunction "1_1") (pintype "passive"))
      (node (ref "R50") (pin "2") (pinfunction "2_2") (pintype "passive"))
    )
    (net (code "93") (name "Net-(IC9B-+IN)") (class "Default")
      (node (ref "IC9") (pin "5") (pinfunction "+IN_5") (pintype "input"))
      (node (ref "R39") (pin "2") (pinfunction "2_2") (pintype "passive"))
      (node (ref "R43") (pin "1") (pinfunction "1_1") (pintype "passive"))
    )
    (net (code "94") (name "Net-(IC9B--IN)") (class "Default")
      (node (ref "C42") (pin "1") (pinfunction "1_1") (pintype "passive"))
      (node (ref "IC9") (pin "6") (pinfunction "-IN_6") (pintype "input"))
      (node (ref "R44") (pin "1") (pinfunction "1_1") (pintype "passive"))
      (node (ref "R48") (pin "2") (pinfunction "2_2") (pintype "passive"))
    )
    (net (code "95") (name "Net-(IC10A-+IN)") (class "Default")
      (node (ref "IC10") (pin "3") (pinfunction "+IN_3") (pintype "input"))
      (node (ref "R55") (pin "2") (pinfunction "2_2") (pintype "passive"))
    )
    (net (code "96") (name "Net-(IC10A--IN)") (class "Default")
      (node (ref "C57") (pin "1") (pinfunction "1_1") (pintype "passive"))
      (node (ref "IC10") (pin "2") (pinfunction "-IN_2") (pintype "input"))
      (node (ref "R57") (pin "2") (pinfunction "2_2") (pintype "passive"))
      (node (ref "R58") (pin "2") (pinfunction "2_2") (pintype "passive"))
      (node (ref "R62") (pin "2") (pinfunction "2_2") (pintype "passive"))
    )
    (net (code "97") (name "Net-(IC10B-+IN)") (class "Default")
      (node (ref "C39") (pin "1") (pinfunction "1_1") (pintype "passive"))
      (node (ref "IC10") (pin "5") (pinfunction "+IN_5") (pintype "input"))
      (node (ref "R30") (pin "2") (pinfunction "2_2") (pintype "passive"))
      (node (ref "R36") (pin "1") (pinfunction "1_1") (pintype "passive"))
    )
    (net (code "98") (name "Net-(IC12A-~{CLR})") (class "Default")
      (node (ref "D14") (pin "A") (pinfunction "A_A") (pintype "passive"))
      (node (ref "D15") (pin "A") (pinfunction "A_A") (pintype "passive"))
      (node (ref "IC12") (pin "6") (pinfunction "~{CLR}_6") (pintype "input"))
      (node (ref "R66") (pin "2") (pinfunction "2_2") (pintype "passive"))
    )
    (net (code "99") (name "Net-(IC13-~{RESET})") (class "Default")
      (node (ref "C60") (pin "1") (pinfunction "1_1") (pintype "passive"))
      (node (ref "IC13") (pin "18") (pinfunction "~{RESET}_18") (pintype "input"))
      (node (ref "JP1") (pin "2") (pinfunction "2_2") (pintype "passive"))
      (node (ref "R64") (pin "2") (pinfunction "2_2") (pintype "passive"))
    )
    (net (code "100") (name "Net-(IC14-TRIM{slash}NR)") (class "Default")
      (node (ref "C68") (pin "1") (pinfunction "1_1") (pintype "passive"))
      (node (ref "IC14") (pin "5") (pinfunction "TRIM/NR_5") (pintype "input"))
    )
    (net (code "101") (name "Net-(IC16-VOUTA)") (class "Default")
      (node (ref "IC16") (pin "4") (pinfunction "VOUTA_4") (pintype "output"))
      (node (ref "I_SET") (pin "1") (pinfunction "1_1") (pintype "passive"))
    )
    (net (code "102") (name "Net-(IC16-VOUTB)") (class "Default")
      (node (ref "IC16") (pin "3") (pinfunction "VOUTB_3") (pintype "output"))
      (node (ref "U_SET") (pin "1") (pinfunction "1_1") (pintype "passive"))
    )
    (net (code "103") (name "Net-(IC17-NO)") (class "Default")
      (node (ref "C72") (pin "2") (pinfunction "2_2") (pintype "passive"))
      (node (ref "IC17") (pin "1") (pinfunction "NO_1") (pintype "bidirectional"))
      (node (ref "R70") (pin "1") (pinfunction "1_1") (pintype "passive"))
      (node (ref "ZD3") (pin "3") (pinfunction "C_3") (pintype "passive"))
    )
    (net (code "104") (name "Net-(IC18-AIN0{slash}REFP1)") (class "Default")
      (node (ref "C76") (pin "2") (pinfunction "2_2") (pintype "passive"))
      (node (ref "IC18") (pin "11") (pinfunction "AIN0/REFP1_11") (pintype "input"))
      (node (ref "R75") (pin "2") (pinfunction "2_2") (pintype "passive"))
    )
    (net (code "105") (name "Net-(IC18-AIN1)") (class "Default")
      (node (ref "C73") (pin "2") (pinfunction "2_2") (pintype "passive"))
      (node (ref "IC18") (pin "10") (pinfunction "AIN1_10") (pintype "input"))
      (node (ref "R72") (pin "2") (pinfunction "2_2") (pintype "passive"))
    )
    (net (code "106") (name "Net-(IC18-AIN2)") (class "Default")
      (node (ref "C74") (pin "2") (pinfunction "2_2") (pintype "passive"))
      (node (ref "IC18") (pin "7") (pinfunction "AIN2_7") (pintype "input"))
      (node (ref "R73") (pin "2") (pinfunction "2_2") (pintype "passive"))
    )
    (net (code "107") (name "Net-(IC18-AIN3{slash}REFN1)") (class "Default")
      (node (ref "C75") (pin "1") (pinfunction "1_1") (pintype "passive"))
      (node (ref "IC18") (pin "6") (pinfunction "AIN3/REFN1_6") (pintype "input"))
      (node (ref "R76") (pin "2") (pinfunction "2_2") (pintype "passive"))
    )
    (net (code "108") (name "Net-(IC18-AVDD)") (class "Default")
      (node (ref "C79") (pin "2") (pinfunction "2_2") (pintype "passive"))
      (node (ref "C80") (pin "2") (pinfunction "2_2") (pintype "passive"))
      (node (ref "IC18") (pin "12") (pinfunction "AVDD_12") (pintype "power_in"))
      (node (ref "R77") (pin "2") (pinfunction "2_2") (pintype "passive"))
    )
    (net (code "109") (name "Net-(IC19A-+IN)") (class "Default")
      (node (ref "IC19") (pin "3") (pinfunction "+IN_3") (pintype "input"))
      (node (ref "IC19") (pin "5") (pinfunction "+IN_5") (pintype "input"))
      (node (ref "R89") (pin "1") (pinfunction "1_1") (pintype "passive"))
    )
    (net (code "110") (name "Net-(IC19A--IN)") (class "Default")
      (node (ref "IC19") (pin "2") (pinfunction "-IN_2") (pintype "input"))
      (node (ref "R81") (pin "2") (pinfunction "2_2") (pintype "passive"))
    )
    (net (code "111") (name "Net-(IC19A-OUT)") (class "Default")
      (node (ref "IC19") (pin "1") (pinfunction "OUT_1") (pintype "output"))
      (node (ref "R82") (pin "1") (pinfunction "1_1") (pintype "passive"))
    )
    (net (code "112") (name "Net-(IC19B--IN)") (class "Default")
      (node (ref "IC19") (pin "6") (pinfunction "-IN_6") (pintype "input"))
      (node (ref "R93") (pin "2") (pinfunction "2_2") (pintype "passive"))
    )
    (net (code "113") (name "Net-(IC19B-OUT)") (class "Default")
      (node (ref "IC19") (pin "7") (pinfunction "OUT_7") (pintype "output"))
      (node (ref "R94") (pin "1") (pinfunction "1_1") (pintype "passive"))
    )
    (net (code "114") (name "Net-(IC20-+IN)") (class "Default")
      (node (ref "C84") (pin "2") (pinfunction "2_2") (pintype "passive"))
      (node (ref "IC20") (pin "2") (pinfunction "+IN_2") (pintype "input"))
      (node (ref "R78") (pin "2") (pinfunction "2_2") (pintype "passive"))
      (node (ref "R83") (pin "1") (pinfunction "1_1") (pintype "passive"))
    )
    (net (code "115") (name "Net-(IC20--IN)") (class "Default")
      (node (ref "C85") (pin "2") (pinfunction "2_2") (pintype "passive"))
      (node (ref "IC20") (pin "3") (pinfunction "-IN_3") (pintype "input"))
      (node (ref "R88") (pin "2") (pinfunction "2_2") (pintype "passive"))
    )
    (net (code "116") (name "Net-(IC20-OUT)") (class "Default")
      (node (ref "IC20") (pin "7") (pinfunction "OUT_7") (pintype "output"))
      (node (ref "Q17") (pin "1") (pinfunction "G_1") (pintype "passive"))
      (node (ref "R85") (pin "2") (pinfunction "2_2") (pintype "passive"))
    )
    (net (code "117") (name "Net-(K1A--)") (class "Default")
      (node (ref "D19") (pin "A") (pinfunction "A_A") (pintype "passive"))
      (node (ref "K1") (pin "8") (pinfunction "-_8") (pintype "passive"))
      (node (ref "Q21") (pin "3") (pinfunction "D_3") (pintype "passive"))
      (node (ref "R105") (pin "1") (pinfunction "1_1") (pintype "passive"))
    )
    (net (code "118") (name "Net-(K1B-S)") (class "Default")
      (node (ref "K1") (pin "4") (pinfunction "S_4") (pintype "passive"))
      (node (ref "X3") (pin "4") (pinfunction "1_4") (pintype "passive"))
    )
    (net (code "119") (name "Net-(K1C-S)") (class "Default")
      (node (ref "K1") (pin "5") (pinfunction "S_5") (pintype "passive"))
      (node (ref "X3") (pin "5") (pinfunction "1_5") (pintype "passive"))
    )
    (net (code "120") (name "Net-(LED1-C)") (class "Default")
      (node (ref "LED1") (pin "CC") (pinfunction "C_CC") (pintype "passive"))
      (node (ref "R68") (pin "1") (pinfunction "1_1") (pintype "passive"))
    )
    (net (code "121") (name "Net-(LED2A-C)") (class "Default")
      (node (ref "LED2") (pin "BC") (pinfunction "C_BC") (pintype "passive"))
      (node (ref "R74") (pin "2") (pinfunction "2_2") (pintype "passive"))
    )
    (net (code "122") (name "Net-(LED2B-C)") (class "Default")
      (node (ref "LED2") (pin "TC") (pinfunction "C_TC") (pintype "passive"))
      (node (ref "R105") (pin "2") (pinfunction "2_2") (pintype "passive"))
    )
    (net (code "123") (name "Net-(LED3A-C)") (class "Default")
      (node (ref "LED3") (pin "BC") (pinfunction "C_BC") (pintype "passive"))
      (node (ref "R86") (pin "2") (pinfunction "2_2") (pintype "passive"))
    )
    (net (code "124") (name "Net-(LED3B-C)") (class "Default")
      (node (ref "LED3") (pin "TC") (pinfunction "C_TC") (pintype "passive"))
      (node (ref "R84") (pin "1") (pinfunction "1_1") (pintype "passive"))
    )
    (net (code "125") (name "Net-(Q3-B)") (class "Default")
      (node (ref "Q3") (pin "1") (pinfunction "B_1") (pintype "passive"))
      (node (ref "R33") (pin "2") (pinfunction "2_2") (pintype "passive"))
    )
    (net (code "126") (name "Net-(Q3-E)") (class "Default")
      (node (ref "Q3") (pin "3") (pinfunction "E_3") (pintype "passive"))
      (node (ref "R25") (pin "2") (pinfunction "2_2") (pintype "passive"))
    )
    (net (code "127") (name "Net-(Q4-B)") (class "Default")
      (node (ref "Q4") (pin "1") (pinfunction "B_1") (pintype "passive"))
      (node (ref "R34") (pin "2") (pinfunction "2_2") (pintype "passive"))
    )
    (net (code "128") (name "Net-(Q4-E)") (class "Default")
      (node (ref "Q4") (pin "3") (pinfunction "E_3") (pintype "passive"))
      (node (ref "R26") (pin "2") (pinfunction "2_2") (pintype "passive"))
    )
    (net (code "129") (name "Net-(Q5-G)") (class "Default")
      (node (ref "Q5") (pin "1") (pinfunction "G_1") (pintype "passive"))
      (node (ref "Q6") (pin "2") (pinfunction "C_2") (pintype "passive"))
      (node (ref "Q6") (pin "4") (pinfunction "C_4") (pintype "passive"))
      (node (ref "R29") (pin "2") (pinfunction "2_2") (pintype "passive"))
      (node (ref "ZD2") (pin "A") (pinfunction "A_A") (pintype "passive"))
    )
    (net (code "130") (name "Net-(Q5-S)") (class "Default")
      (node (ref "Q5") (pin "3") (pinfunction "S_3") (pintype "passive"))
      (node (ref "R28") (pin "1") (pinfunction "1_1") (pintype "passive"))
    )
    (net (code "131") (name "Net-(Q6-B)") (class "Default")
      (node (ref "Q6") (pin "1") (pinfunction "B_1") (pintype "passive"))
      (node (ref "R35") (pin "1") (pinfunction "1_1") (pintype "passive"))
      (node (ref "R37") (pin "1") (pinfunction "1_1") (pintype "passive"))
    )
    (net (code "132") (name "Net-(Q6-E)") (class "Default")
      (node (ref "Q6") (pin "3") (pinfunction "E_3") (pintype "passive"))
      (node (ref "R38") (pin "1") (pinfunction "1_1") (pintype "passive"))
    )
    (net (code "133") (name "Net-(Q8-C-Pad2)") (class "Default")
      (node (ref "Q8") (pin "2") (pinfunction "C_2") (pintype "passive"))
      (node (ref "Q8") (pin "4") (pinfunction "C_4") (pintype "passive"))
      (node (ref "R32") (pin "1") (pinfunction "1_1") (pintype "passive"))
      (node (ref "R33") (pin "1") (pinfunction "1_1") (pintype "passive"))
      (node (ref "R34") (pin "1") (pinfunction "1_1") (pintype "passive"))
    )
    (net (code "134") (name "Net-(Q8-E)") (class "Default")
      (node (ref "Q8") (pin "3") (pinfunction "E_3") (pintype "passive"))
      (node (ref "R47") (pin "2") (pinfunction "2_2") (pintype "passive"))
    )
    (net (code "135") (name "Net-(Q9-D)") (class "Default")
      (node (ref "Q9") (pin "3") (pinfunction "D_3") (pintype "passive"))
      (node (ref "R47") (pin "1") (pinfunction "1_1") (pintype "passive"))
    )
    (net (code "136") (name "Net-(Q10-S-Pad1)") (class "Default")
      (node (ref "Q10") (pin "1") (pinfunction "S_1") (pintype "passive"))
      (node (ref "Q10") (pin "2") (pinfunction "S_2") (pintype "passive"))
      (node (ref "Q10") (pin "3") (pinfunction "S_3") (pintype "passive"))
      (node (ref "R53") (pin "1") (pinfunction "1_1") (pintype "passive"))
      (node (ref "R56") (pin "1") (pinfunction "1_1") (pintype "passive"))
    )
    (net (code "137") (name "Net-(Q11-S-Pad1)") (class "Default")
      (node (ref "Q11") (pin "1") (pinfunction "S_1") (pintype "passive"))
      (node (ref "Q11") (pin "2") (pinfunction "S_2") (pintype "passive"))
      (node (ref "Q11") (pin "3") (pinfunction "S_3") (pintype "passive"))
      (node (ref "R61") (pin "2") (pinfunction "2_2") (pintype "passive"))
    )
    (net (code "138") (name "Net-(Q12-D)") (class "Default")
      (node (ref "Q12") (pin "3") (pinfunction "D_3") (pintype "passive"))
      (node (ref "R69") (pin "2") (pinfunction "2_2") (pintype "passive"))
    )
    (net (code "139") (name "Net-(Q13-PadA2)") (class "Default")
      (node (ref "Q13") (pin "A2") (pinfunction "A2_A2") (pintype "passive"))
      (node (ref "R87") (pin "2") (pinfunction "2_2") (pintype "passive"))
    )
    (net (code "140") (name "Net-(Q13-PadG)") (class "Default")
      (node (ref "Q13") (pin "G") (pinfunction "G_G") (pintype "passive"))
      (node (ref "Q14") (pin "C") (pinfunction "C_C") (pintype "passive"))
      (node (ref "R80") (pin "1") (pinfunction "1_1") (pintype "passive"))
    )
    (net (code "141") (name "Net-(Q14-PadE)") (class "Default")
      (node (ref "Q14") (pin "E") (pinfunction "E_E") (pintype "passive"))
      (node (ref "R91") (pin "2") (pinfunction "2_2") (pintype "passive"))
    )
    (net (code "142") (name "Net-(Q15-D)") (class "Default")
      (node (ref "Q15") (pin "3") (pinfunction "D_3") (pintype "passive"))
      (node (ref "R84") (pin "2") (pinfunction "2_2") (pintype "passive"))
    )
    (net (code "143") (name "Net-(Q16-D)") (class "Default")
      (node (ref "Q16") (pin "3") (pinfunction "D_3") (pintype "passive"))
      (node (ref "R86") (pin "1") (pinfunction "1_1") (pintype "passive"))
    )
    (net (code "144") (name "Net-(Q18-PadC)") (class "Default")
      (node (ref "Q18") (pin "C") (pinfunction "C_C") (pintype "passive"))
      (node (ref "R100") (pin "2") (pinfunction "2_2") (pintype "passive"))
    )
    (net (code "145") (name "Net-(Q19-PadB)") (class "Default")
      (node (ref "Q19") (pin "B") (pinfunction "B_B") (pintype "passive"))
      (node (ref "R100") (pin "1") (pinfunction "1_1") (pintype "passive"))
      (node (ref "R103") (pin "2") (pinfunction "2_2") (pintype "passive"))
    )
    (net (code "146") (name "Net-(Q20-PadC)") (class "Default")
      (node (ref "Q20") (pin "C") (pinfunction "C_C") (pintype "passive"))
      (node (ref "R97") (pin "1") (pinfunction "1_1") (pintype "passive"))
    )
    (net (code "147") (name "Net-(R27-Pad1)") (class "Default")
      (node (ref "R27") (pin "1") (pinfunction "1_1") (pintype "passive"))
      (node (ref "R31") (pin "2") (pinfunction "2_2") (pintype "passive"))
    )
    (net (code "148") (name "Net-(R56-Pad2)") (class "Default")
      (node (ref "R56") (pin "2") (pinfunction "2_2") (pintype "passive"))
      (node (ref "R61") (pin "2S") (pinfunction "2S_2S") (pintype "passive"))
    )
    (net (code "149") (name "Net-(R61-Pad1S)") (class "Default")
      (node (ref "R61") (pin "1S") (pinfunction "1S_1S") (pintype "passive"))
      (node (ref "R63") (pin "1") (pinfunction "1_1") (pintype "passive"))
    )
    (net (code "150") (name "Net-(R70-Pad2)") (class "Default")
      (node (ref "R70") (pin "2") (pinfunction "2_2") (pintype "passive"))
      (node (ref "R71") (pin "1") (pinfunction "1_1") (pintype "passive"))
    )
    (net (code "151") (name "Net-(R71-Pad2)") (class "Default")
      (node (ref "R71") (pin "2") (pinfunction "2_2") (pintype "passive"))
      (node (ref "X3") (pin "1") (pinfunction "1_1") (pintype "passive"))
    )
    (net (code "152") (name "Net-(R97-Pad2)") (class "Default")
      (node (ref "R97") (pin "2") (pinfunction "2_2") (pintype "passive"))
      (node (ref "R98") (pin "1") (pinfunction "1_1") (pintype "passive"))
    )
    (net (code "153") (name "OE") (class "Default")
      (node (ref "IC13") (pin "2") (pinfunction "GPB1_2") (pintype "bidirectional"))
      (node (ref "OE") (pin "1") (pinfunction "1_1") (pintype "passive"))
    )
    (net (code "154") (name "OE_GREEN") (class "Default")
      (node (ref "IC13") (pin "7") (pinfunction "GPB6_7") (pintype "bidirectional"))
      (node (ref "LED1") (pin "GREEN") (pinfunction "AG_GREEN") (pintype "passive"))
    )
    (net (code "155") (name "OE_RED") (class "Default")
      (node (ref "IC13") (pin "8") (pinfunction "GPB7_8") (pintype "bidirectional"))
      (node (ref "LED1") (pin "RED") (pinfunction "AR_RED") (pintype "passive"))
    )
    (net (code "156") (name "OE_SYNC") (class "Default")
      (node (ref "IC7") (pin "4") (pinfunction "A2_4") (pintype "input"))
      (node (ref "X2") (pin "6") (pinfunction "1_6") (pintype "passive"))
    )
    (net (code "157") (name "OE_TRIG") (class "Default")
      (node (ref "IC12") (pin "1") (pinfunction "CLK_1") (pintype "input"))
      (node (ref "RN2") (pin "5") (pinfunction "2_5") (pintype "passive"))
    )
    (net (code "158") (name "OUTC+") (class "Default")
      (node (ref "C91") (pin "1") (pinfunction "1_1") (pintype "passive"))
      (node (ref "C92") (pin "+") (pinfunction "+_+") (pintype "passive"))
      (node (ref "C93") (pin "1") (pinfunction "1_1") (pintype "passive"))
      (node (ref "C94") (pin "1") (pinfunction "1_1") (pintype "passive"))
      (node (ref "J2") (pin "1") (pinfunction "1_1") (pintype "passive"))
      (node (ref "J2") (pin "NC1") (pinfunction "1_NC1") (pintype "passive"))
      (node (ref "J2") (pin "NC2") (pinfunction "1_NC2") (pintype "passive"))
      (node (ref "J2") (pin "NC3") (pinfunction "1_NC3") (pintype "passive"))
      (node (ref "J2") (pin "NC4") (pinfunction "1_NC4") (pintype "passive"))
      (node (ref "X4") (pin "1") (pinfunction "1_1") (pintype "passive"))
      (node (ref "X4") (pin "2") (pinfunction "1_2") (pintype "passive"))
      (node (ref "X4") (pin "3") (pinfunction "1_3") (pintype "passive"))
      (node (ref "X4") (pin "4") (pinfunction "1_4") (pintype "passive"))
      (node (ref "X4") (pin "5") (pinfunction "1_5") (pintype "passive"))
    )
    (net (code "159") (name "OUTC-") (class "Default")
      (node (ref "C92") (pin "-") (pinfunction "-_-") (pintype "passive"))
      (node (ref "C93") (pin "2") (pinfunction "2_2") (pintype "passive"))
      (node (ref "C94") (pin "2") (pinfunction "2_2") (pintype "passive"))
      (node (ref "C95") (pin "2") (pinfunction "2_2") (pintype "passive"))
      (node (ref "J3") (pin "1") (pinfunction "1_1") (pintype "passive"))
      (node (ref "J3") (pin "NC1") (pinfunction "1_NC1") (pintype "passive"))
      (node (ref "J3") (pin "NC2") (pinfunction "1_NC2") (pintype "passive"))
      (node (ref "J3") (pin "NC3") (pinfunction "1_NC3") (pintype "passive"))
      (node (ref "J3") (pin "NC4") (pinfunction "1_NC4") (pintype "passive"))
      (node (ref "X4") (pin "16") (pinfunction "1_16") (pintype "passive"))
      (node (ref "X4") (pin "17") (pinfunction "1_17") (pintype "passive"))
      (node (ref "X4") (pin "18") (pinfunction "1_18") (pintype "passive"))
      (node (ref "X4") (pin "19") (pinfunction "1_19") (pintype "passive"))
      (node (ref "X4") (pin "20") (pinfunction "1_20") (pintype "passive"))
    )
    (net (code "160") (name "OUTF+") (class "Default")
      (node (ref "F2") (pin "2") (pinfunction "2_2") (pintype "passive"))
      (node (ref "Q13") (pin "A1") (pinfunction "A1_A1") (pintype "passive"))
      (node (ref "R80") (pin "2") (pinfunction "2_2") (pintype "passive"))
      (node (ref "X4") (pin "10") (pinfunction "1_10") (pintype "passive"))
      (node (ref "X4") (pin "6") (pinfunction "1_6") (pintype "passive"))
      (node (ref "X4") (pin "7") (pinfunction "1_7") (pintype "passive"))
      (node (ref "X4") (pin "8") (pinfunction "1_8") (pintype "passive"))
      (node (ref "X4") (pin "9") (pinfunction "1_9") (pintype "passive"))
    )
    (net (code "161") (name "OVP_EN") (class "Default")
      (node (ref "IC13") (pin "5") (pinfunction "GPB4_5") (pintype "bidirectional"))
      (node (ref "IC20") (pin "6") (pinfunction "~{SHDN}_6") (pintype "input"))
    )
    (net (code "162") (name "PE") (class "Default")
      (node (ref "C3") (pin "2") (pinfunction "2_2") (pintype "passive"))
      (node (ref "C4") (pin "1") (pinfunction "1_1") (pintype "passive"))
      (node (ref "C91") (pin "2") (pinfunction "2_2") (pintype "passive"))
      (node (ref "C95") (pin "1") (pinfunction "1_1") (pintype "passive"))
      (node (ref "J1") (pin "1") (pinfunction "P$1_1") (pintype "bidirectional"))
      (node (ref "J1") (pin "2") (pinfunction "P$1_2") (pintype "bidirectional"))
      (node (ref "X3") (pin "3") (pinfunction "1_3") (pintype "passive"))
    )
    (net (code "163") (name "POST_OE") (class "Default")
      (node (ref "IC12") (pin "5") (pinfunction "Q_5") (pintype "output"))
      (node (ref "Q9") (pin "1") (pinfunction "G_1") (pintype "passive"))
      (node (ref "R51") (pin "2") (pinfunction "2_2") (pintype "passive"))
    )
    (net (code "164") (name "POST_OUT+") (class "Default")
      (node (ref "C44") (pin "1") (pinfunction "1_1") (pintype "passive"))
      (node (ref "C59") (pin "1") (pinfunction "1_1") (pintype "passive"))
      (node (ref "D8") (pin "A") (pinfunction "A_A") (pintype "passive"))
      (node (ref "F1") (pin "1") (pinfunction "1_1") (pintype "passive"))
      (node (ref "Q3") (pin "2") (pinfunction "C_2") (pintype "passive"))
      (node (ref "Q4") (pin "2") (pinfunction "C_2") (pintype "passive"))
      (node (ref "R10") (pin "2") (pinfunction "2_2") (pintype "passive"))
      (node (ref "R27") (pin "2") (pinfunction "2_2") (pintype "passive"))
      (node (ref "R28") (pin "2") (pinfunction "2_2") (pintype "passive"))
      (node (ref "R29") (pin "1") (pinfunction "1_1") (pintype "passive"))
      (node (ref "ZD2") (pin "C") (pinfunction "C_C") (pintype "passive"))
    )
    (net (code "165") (name "POST_OUT-") (class "Default")
      (node (ref "C41") (pin "1") (pinfunction "1_1") (pintype "passive"))
      (node (ref "C90") (pin "-") (pinfunction "-_-") (pintype "passive"))
      (node (ref "C96") (pin "2") (pinfunction "2_2") (pintype "passive"))
      (node (ref "D13") (pin "A") (pinfunction "A_A") (pintype "passive"))
      (node (ref "D18") (pin "1") (pinfunction "A_1") (pintype "passive"))
      (node (ref "D18") (pin "2") (pinfunction "A_2") (pintype "passive"))
      (node (ref "JP4") (pin "1") (pinfunction "1_1") (pintype "passive"))
      (node (ref "K1") (pin "7") (pinfunction "O_7") (pintype "passive"))
      (node (ref "Q10") (pin "MB") (pinfunction "D_MB") (pintype "passive"))
      (node (ref "Q11") (pin "MB") (pinfunction "D_MB") (pintype "passive"))
      (node (ref "Q20") (pin "E") (pinfunction "E_E") (pintype "passive"))
      (node (ref "R101") (pin "1") (pinfunction "1_1") (pintype "passive"))
      (node (ref "R104") (pin "1") (pinfunction "1_1") (pintype "passive"))
      (node (ref "X4") (pin "11") (pinfunction "1_11") (pintype "passive"))
      (node (ref "X4") (pin "12") (pinfunction "1_12") (pintype "passive"))
      (node (ref "X4") (pin "13") (pinfunction "1_13") (pintype "passive"))
      (node (ref "X4") (pin "14") (pinfunction "1_14") (pintype "passive"))
      (node (ref "X4") (pin "15") (pinfunction "1_15") (pintype "passive"))
    )
    (net (code "166") (name "PREG_IN-") (class "Default")
      (node (ref "C10") (pin "2") (pinfunction "2_2") (pintype "passive"))
      (node (ref "C11") (pin "-") (pinfunction "-_-") (pintype "passive"))
      (node (ref "C15") (pin "2") (pinfunction "2_2") (pintype "passive"))
      (node (ref "C16") (pin "-") (pinfunction "-_-") (pintype "passive"))
      (node (ref "C2") (pin "-") (pinfunction "-_-") (pintype "passive"))
      (node (ref "C3") (pin "1") (pinfunction "1_1") (pintype "passive"))
      (node (ref "C5") (pin "2") (pinfunction "2_2") (pintype "passive"))
      (node (ref "C6") (pin "2") (pinfunction "2_2") (pintype "passive"))
      (node (ref "C7") (pin "2") (pinfunction "2_2") (pintype "passive"))
      (node (ref "D2") (pin "1") (pinfunction "A_1") (pintype "passive"))
      (node (ref "D2") (pin "2") (pinfunction "A_2") (pintype "passive"))
      (node (ref "IC1") (pin "TP") (pinfunction "PGND_TP") (pintype "passive"))
      (node (ref "L1") (pin "4") (pinfunction "2_4") (pintype "passive"))
      (node (ref "R2") (pin "1") (pinfunction "1_1") (pintype "passive"))
      (node (ref "R5") (pin "1") (pinfunction "1_1") (pintype "passive"))
      (node (ref "SH1") (pin "1") (pinfunction "GND_A_1") (pintype "bidirectional"))
      (node (ref "SH2") (pin "2") (pinfunction "GND_B_2") (pintype "bidirectional"))
      (node (ref "SH3") (pin "2") (pinfunction "GND_B_2") (pintype "bidirectional"))
      (node (ref "ZD1") (pin "A") (pinfunction "A_A") (pintype "passive"))
    )
    (net (code "167") (name "PREG_OUT+") (class "Default")
      (node (ref "C13") (pin "+") (pinfunction "+_+") (pintype "passive"))
      (node (ref "C14") (pin "1") (pinfunction "1_1") (pintype "passive"))
      (node (ref "D8") (pin "C") (pinfunction "C_C") (pintype "passive"))
      (node (ref "L3") (pin "2") (pinfunction "2_2") (pintype "passive"))
      (node (ref "R25") (pin "1") (pinfunction "1_1") (pintype "passive"))
      (node (ref "R26") (pin "1") (pinfunction "1_1") (pintype "passive"))
      (node (ref "R32") (pin "2") (pinfunction "2_2") (pintype "passive"))
      (node (ref "R4") (pin "2") (pinfunction "2_2") (pintype "passive"))
    )
    (net (code "168") (name "PREG_OUT-") (class "Default")
      (node (ref "C13") (pin "-") (pinfunction "-_-") (pintype "passive"))
      (node (ref "C14") (pin "2") (pinfunction "2_2") (pintype "passive"))
      (node (ref "D13") (pin "C") (pinfunction "C_C") (pintype "passive"))
      (node (ref "Q5") (pin "2") (pinfunction "D_2") (pintype "passive"))
      (node (ref "R31") (pin "1") (pinfunction "1_1") (pintype "passive"))
      (node (ref "R61") (pin "1") (pinfunction "1_1") (pintype "passive"))
      (node (ref "R87") (pin "1") (pinfunction "1_1") (pintype "passive"))
      (node (ref "SH2") (pin "1") (pinfunction "GND_A_1") (pintype "bidirectional"))
    )
    (net (code "169") (name "PRE_OE") (class "Default")
      (node (ref "D1") (pin "A") (pinfunction "A_A") (pintype "passive"))
      (node (ref "IC12") (pin "2") (pinfunction "D_2") (pintype "input"))
      (node (ref "OE") (pin "2") (pinfunction "2_2") (pintype "passive"))
    )
    (net (code "170") (name "PWRGOOD") (class "Default")
      (node (ref "D15") (pin "C") (pinfunction "C_C") (pintype "passive"))
      (node (ref "IC13") (pin "24") (pinfunction "GPA3_24") (pintype "bidirectional"))
      (node (ref "IC2") (pin "6") (pinfunction "PWRGD_6") (pintype "output"))
      (node (ref "R17") (pin "2") (pinfunction "2_2") (pintype "passive"))
    )
    (net (code "171") (name "RSENSE") (class "Default")
      (node (ref "IC13") (pin "3") (pinfunction "GPB2_3") (pintype "bidirectional"))
      (node (ref "Q21") (pin "1") (pinfunction "G_1") (pintype "passive"))
      (node (ref "R106") (pin "2") (pinfunction "2_2") (pintype "passive"))
    )
    (net (code "172") (name "SCLK") (class "Default")
      (node (ref "IC13") (pin "12") (pinfunction "SCK_12") (pintype "input"))
      (node (ref "IC15") (pin "3") (pinfunction "SCLK_3") (pintype "input"))
      (node (ref "IC16") (pin "6") (pinfunction "SCLK_6") (pintype "input"))
      (node (ref "IC18") (pin "1") (pinfunction "SCLK_1") (pintype "input"))
      (node (ref "RN2") (pin "8") (pinfunction "2_8") (pintype "passive"))
    )
    (net (code "173") (name "SENSE+") (class "Default")
      (node (ref "JP3") (pin "1") (pinfunction "1_1") (pintype "passive"))
      (node (ref "K1") (pin "3") (pinfunction "P_3") (pintype "passive"))
      (node (ref "R43") (pin "2") (pinfunction "2_2") (pintype "passive"))
      (node (ref "R96") (pin "1") (pinfunction "1_1") (pintype "passive"))
    )
    (net (code "174") (name "SENSE-") (class "Default")
      (node (ref "JP4") (pin "2") (pinfunction "2_2") (pintype "passive"))
      (node (ref "K1") (pin "6") (pinfunction "P_6") (pintype "passive"))
      (node (ref "R102") (pin "2") (pinfunction "2_2") (pintype "passive"))
      (node (ref "R44") (pin "2") (pinfunction "2_2") (pintype "passive"))
    )
    (net (code "175") (name "SENSE_ERR") (class "Default")
      (node (ref "IC13") (pin "21") (pinfunction "GPA0_21") (pintype "bidirectional"))
      (node (ref "Q19") (pin "C") (pinfunction "C_C") (pintype "passive"))
      (node (ref "R99") (pin "1") (pinfunction "1_1") (pintype "passive"))
    )
    (net (code "176") (name "SGND") (class "Default")
      (node (ref "C17") (pin "2") (pinfunction "2_2") (pintype "passive"))
      (node (ref "C18") (pin "2") (pinfunction "2_2") (pintype "passive"))
      (node (ref "C9") (pin "1") (pinfunction "1_1") (pintype "passive"))
      (node (ref "IC1") (pin "1") (pinfunction "PLLIN/MODE_1") (pintype "input"))
      (node (ref "IC1") (pin "2") (pinfunction "FREQ_2") (pintype "input"))
      (node (ref "IC1") (pin "3") (pinfunction "SGND_3") (pintype "passive"))
      (node (ref "R11") (pin "2") (pinfunction "2_2") (pintype "passive"))
      (node (ref "SH3") (pin "1") (pinfunction "GND_A_1") (pintype "bidirectional"))
    )
    (net (code "177") (name "TEMP_CS") (class "Default")
      (node (ref "IC15") (pin "1") (pinfunction "~{CS}_1") (pintype "input"))
      (node (ref "RN1") (pin "5") (pinfunction "2_5") (pintype "passive"))
    )
    (net (code "178") (name "U_MON") (class "Default")
      (node (ref "C42") (pin "2") (pinfunction "2_2") (pintype "passive"))
      (node (ref "IC9") (pin "7") (pinfunction "OUT_7") (pintype "output"))
      (node (ref "R46") (pin "1") (pinfunction "1_1") (pintype "passive"))
      (node (ref "R48") (pin "1") (pinfunction "1_1") (pintype "passive"))
      (node (ref "R75") (pin "1") (pinfunction "1_1") (pintype "passive"))
      (node (ref "R78") (pin "1") (pinfunction "1_1") (pintype "passive"))
    )
    (net (code "179") (name "U_SERVO") (class "Default")
      (node (ref "C43") (pin "2") (pinfunction "2_2") (pintype "passive"))
      (node (ref "C45") (pin "2") (pinfunction "2_2") (pintype "passive"))
      (node (ref "D11") (pin "C") (pinfunction "C_C") (pintype "passive"))
      (node (ref "IC9") (pin "1") (pinfunction "OUT_1") (pintype "output"))
      (node (ref "R41") (pin "1") (pinfunction "1_1") (pintype "passive"))
      (node (ref "R81") (pin "1") (pinfunction "1_1") (pintype "passive"))
    )
    (net (code "180") (name "U_SET") (class "Default")
      (node (ref "IC17") (pin "3") (pinfunction "NC_3") (pintype "bidirectional"))
      (node (ref "JP2") (pin "1") (pinfunction "1_1") (pintype "passive"))
      (node (ref "R73") (pin "1") (pinfunction "1_1") (pintype "passive"))
      (node (ref "R88") (pin "1") (pinfunction "1_1") (pintype "passive"))
      (node (ref "U_SET") (pin "2") (pinfunction "2_2") (pintype "passive"))
    )
    (net (code "181") (name "U_SET_OUT") (class "Default")
      (node (ref "IC17") (pin "4") (pinfunction "COM_4") (pintype "bidirectional"))
      (node (ref "JP2") (pin "2") (pinfunction "2_2") (pintype "passive"))
      (node (ref "R45") (pin "1") (pinfunction "1_1") (pintype "passive"))
    )
    (net (code "182") (name "V+") (class "Default")
      (node (ref "C46") (pin "2") (pinfunction "2_2") (pintype "passive"))
      (node (ref "C47") (pin "1") (pinfunction "1_1") (pintype "passive"))
      (node (ref "C48") (pin "2") (pinfunction "2_2") (pintype "passive"))
      (node (ref "C49") (pin "2") (pinfunction "2_2") (pintype "passive"))
      (node (ref "C50") (pin "2") (pinfunction "2_2") (pintype "passive"))
      (node (ref "C64") (pin "1") (pinfunction "1_1") (pintype "passive"))
      (node (ref "C67") (pin "1") (pinfunction "1_1") (pintype "passive"))
      (node (ref "C69") (pin "2") (pinfunction "2_2") (pintype "passive"))
      (node (ref "C71") (pin "1") (pinfunction "1_1") (pintype "passive"))
      (node (ref "C82") (pin "1") (pinfunction "1_1") (pintype "passive"))
      (node (ref "C83") (pin "2") (pinfunction "2_2") (pintype "passive"))
      (node (ref "C86") (pin "2") (pinfunction "2_2") (pintype "passive"))
      (node (ref "FB1") (pin "P$2") (pinfunction "2_P$2") (pintype "passive"))
      (node (ref "IC10") (pin "8") (pinfunction "V+_8") (pintype "power_in"))
      (node (ref "IC11") (pin "7") (pinfunction "V+_7") (pintype "power_in"))
      (node (ref "IC14") (pin "2") (pinfunction "VIN_2") (pintype "passive"))
      (node (ref "IC16") (pin "1") (pinfunction "VDD_1") (pintype "power_in"))
      (node (ref "IC17") (pin "5") (pinfunction "VDD_5") (pintype "power_in"))
      (node (ref "IC19") (pin "8") (pinfunction "V+_8") (pintype "power_in"))
      (node (ref "IC20") (pin "1") (pinfunction "+VCC_1") (pintype "passive"))
      (node (ref "IC20") (pin "5") (pinfunction "~{LE}_5") (pintype "input"))
      (node (ref "IC9") (pin "8") (pinfunction "V+_8") (pintype "power_in"))
      (node (ref "R40") (pin "2") (pinfunction "2_2") (pintype "passive"))
      (node (ref "R77") (pin "1") (pinfunction "1_1") (pintype "passive"))
    )
    (net (code "183") (name "V-") (class "Default")
      (node (ref "C51") (pin "2") (pinfunction "2_2") (pintype "passive"))
      (node (ref "C53") (pin "2") (pinfunction "2_2") (pintype "passive"))
      (node (ref "C54") (pin "1") (pinfunction "1_1") (pintype "passive"))
      (node (ref "C55") (pin "2") (pinfunction "2_2") (pintype "passive"))
      (node (ref "C56") (pin "2") (pinfunction "2_2") (pintype "passive"))
      (node (ref "C87") (pin "2") (pinfunction "2_2") (pintype "passive"))
      (node (ref "FB3") (pin "P$2") (pinfunction "2_P$2") (pintype "passive"))
      (node (ref "IC10") (pin "4") (pinfunction "V-_4") (pintype "power_in"))
      (node (ref "IC11") (pin "4") (pinfunction "V-_4") (pintype "power_in"))
      (node (ref "IC19") (pin "4") (pinfunction "V-_4") (pintype "power_in"))
      (node (ref "IC9") (pin "4") (pinfunction "V-_4") (pintype "power_in"))
    )
    (net (code "184") (name "unconnected-(IC1-PGOOD-Pad7)") (class "Default")
      (node (ref "IC1") (pin "7") (pinfunction "PGOOD_7") (pintype "output"))
    )
    (net (code "185") (name "unconnected-(IC12A-~{Q}-Pad3)") (class "Default")
      (node (ref "IC12") (pin "3") (pinfunction "~{Q}_3") (pintype "output"))
    )
    (net (code "186") (name "unconnected-(IC13-GPB5-Pad6)") (class "Default")
      (node (ref "IC13") (pin "6") (pinfunction "GPB5_6") (pintype "bidirectional"))
    )
    (net (code "187") (name "unconnected-(IC13-INTB-Pad19)") (class "Default")
      (node (ref "IC13") (pin "19") (pinfunction "INTB_19") (pintype "output"))
    )
    (net (code "188") (name "unconnected-(IC14-TEMP-Pad3)") (class "Default")
      (node (ref "IC14") (pin "3") (pinfunction "TEMP_3") (pintype "input"))
    )
    (net (code "189") (name "~{ADC_DRDY}") (class "Default")
      (node (ref "IC13") (pin "25") (pinfunction "GPA4_25") (pintype "bidirectional"))
      (node (ref "IC18") (pin "14") (pinfunction "~{DRDY}_14") (pintype "output"))
    )
    (net (code "190") (name "~{DP_DRIVE}") (class "Default")
      (node (ref "D9") (pin "A") (pinfunction "A_A") (pintype "passive"))
      (node (ref "Q7") (pin "E") (pinfunction "E_E") (pintype "passive"))
      (node (ref "R69") (pin "1") (pinfunction "1_1") (pintype "passive"))
    )
    (net (code "191") (name "~{OVP_FAULT}") (class "Default")
      (node (ref "C61") (pin "1") (pinfunction "1_1") (pintype "passive"))
      (node (ref "D14") (pin "C") (pinfunction "C_C") (pintype "passive"))
      (node (ref "IC13") (pin "26") (pinfunction "GPA5_26") (pintype "bidirectional"))
      (node (ref "Q17") (pin "3") (pinfunction "D_3") (pintype "passive"))
      (node (ref "R65") (pin "2") (pinfunction "2_2") (pintype "passive"))
    )
    (net (code "192") (name "~{RESET}") (class "Default")
      (node (ref "IC7") (pin "12") (pinfunction "B3_12") (pintype "output"))
      (node (ref "JP1") (pin "1") (pinfunction "1_1") (pintype "passive"))
    )
    (net (code "193") (name "~{SET_DP}") (class "Default")
      (node (ref "IC13") (pin "1") (pinfunction "GPB0_1") (pintype "bidirectional"))
      (node (ref "Q12") (pin "1") (pinfunction "G_1") (pintype "passive"))
      (node (ref "R67") (pin "2") (pinfunction "2_2") (pintype "passive"))
    )
  )
)
